# JETSON.net
KiCad netlist of a schematic drawn in Altium Designer
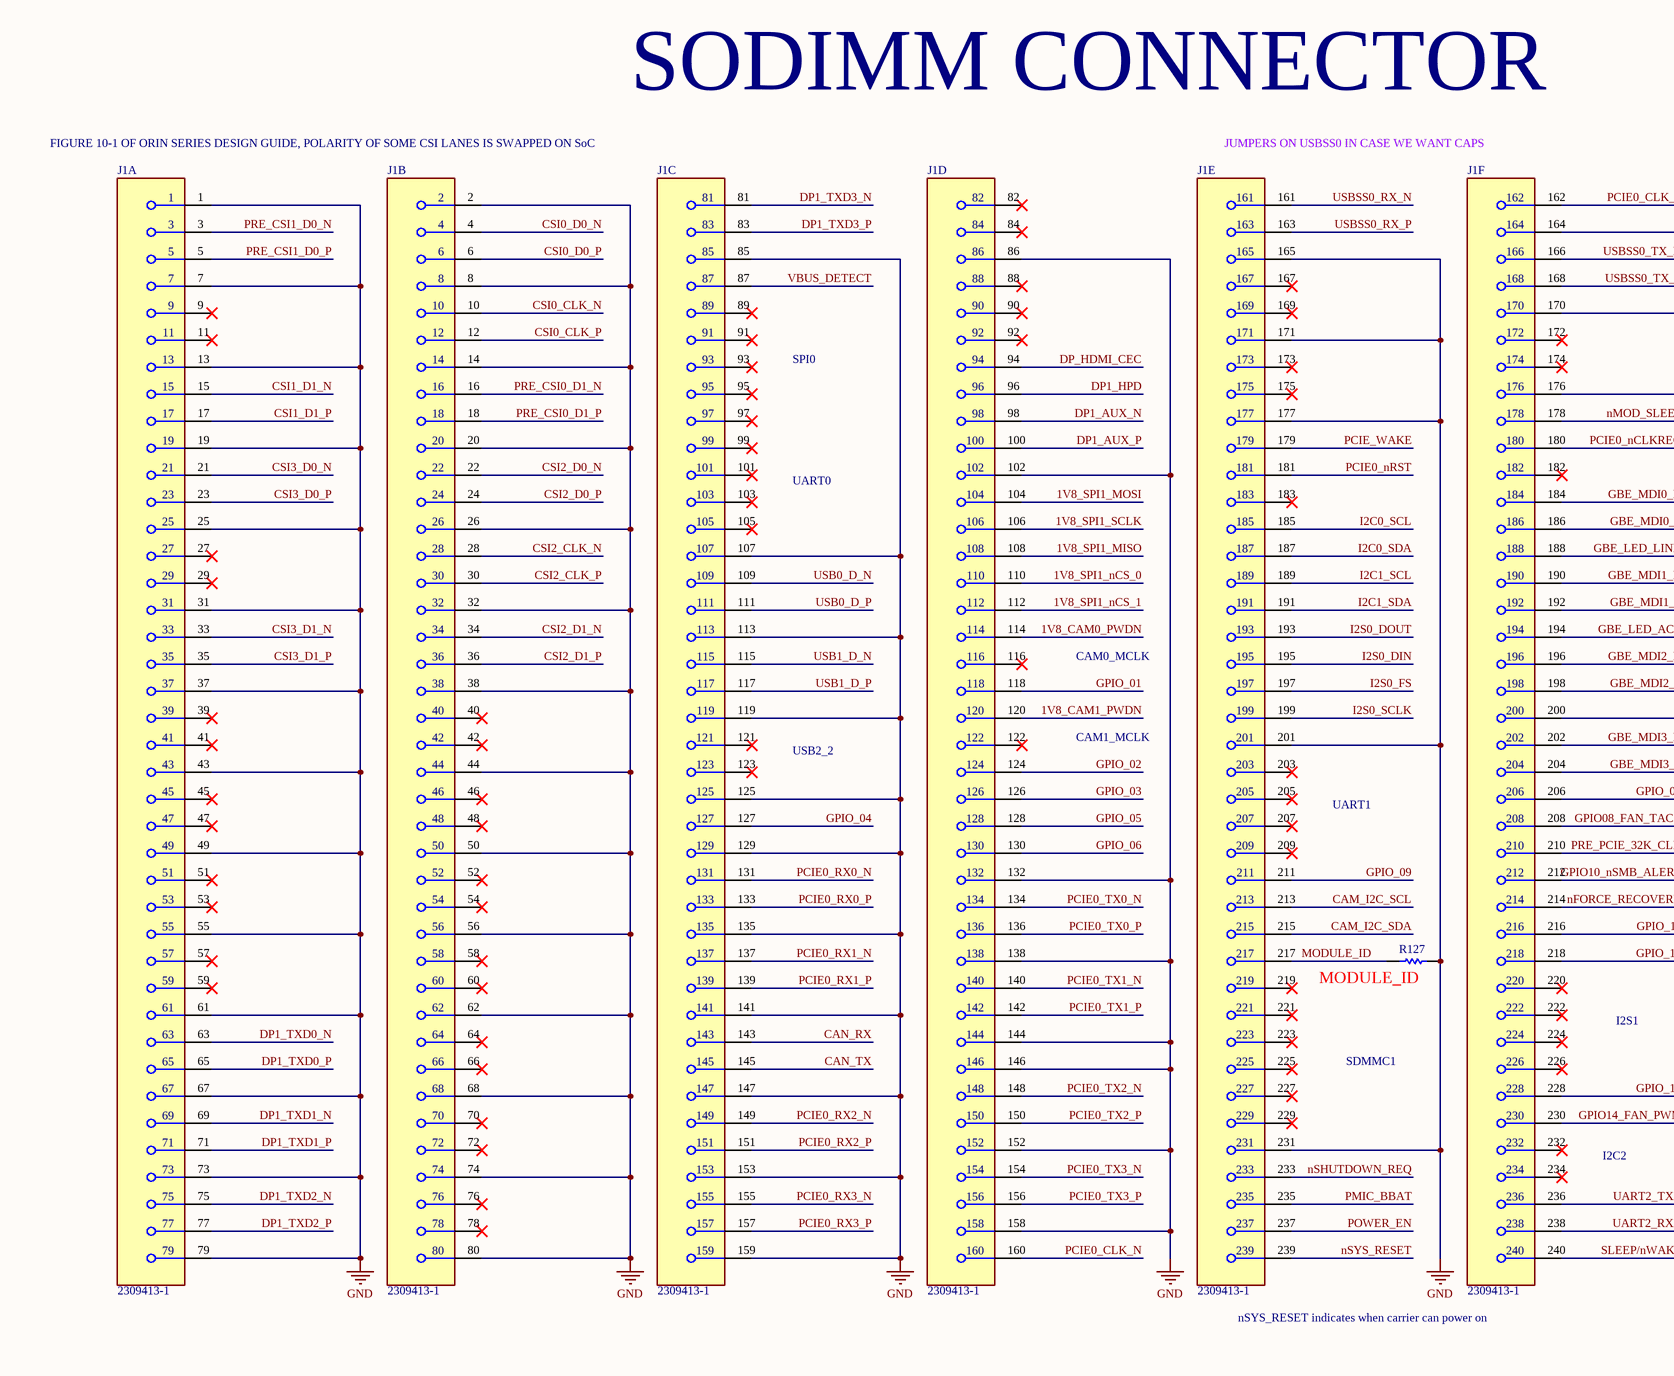
[diagram p0: JETSON.SchDoc, top left]
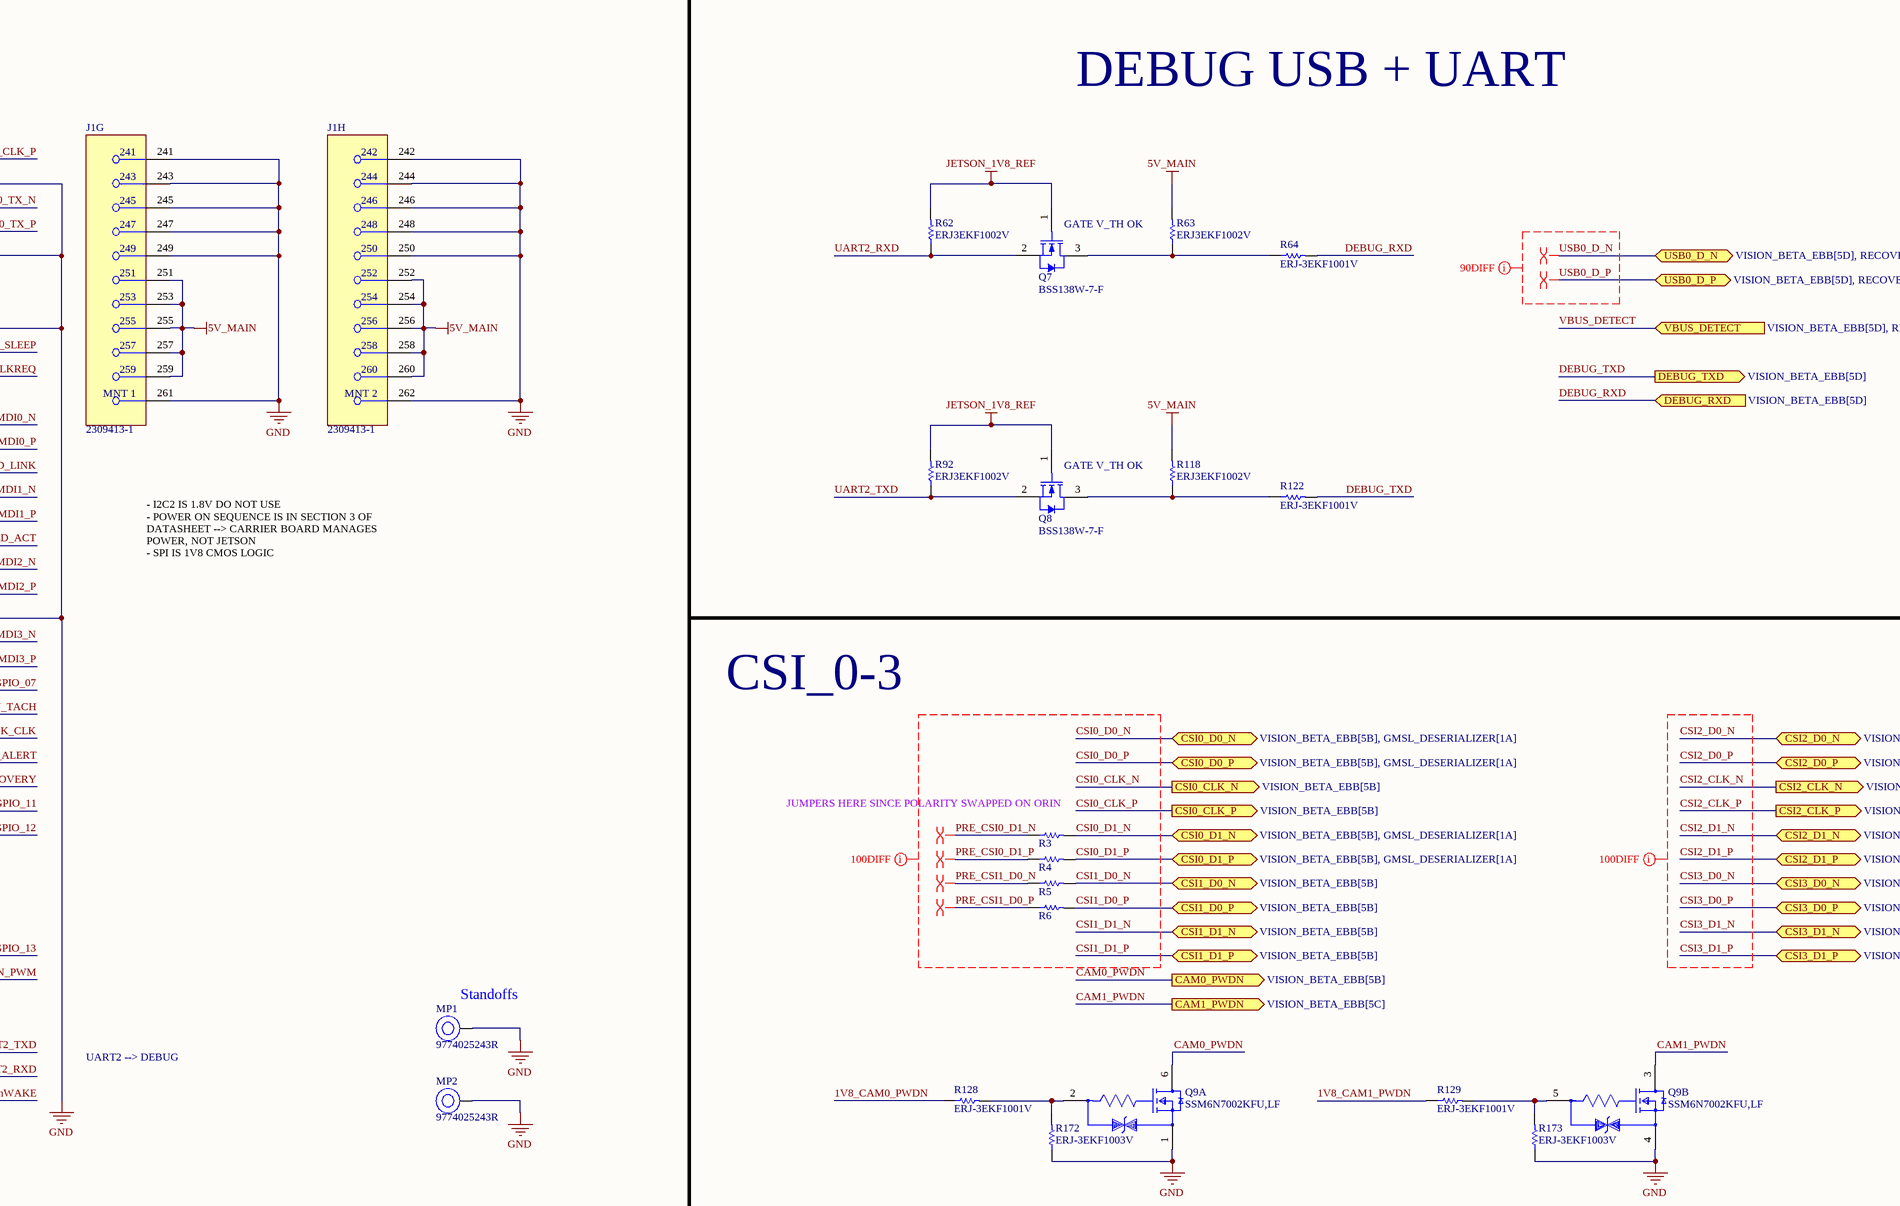
[diagram p1: JETSON.SchDoc, top middle]
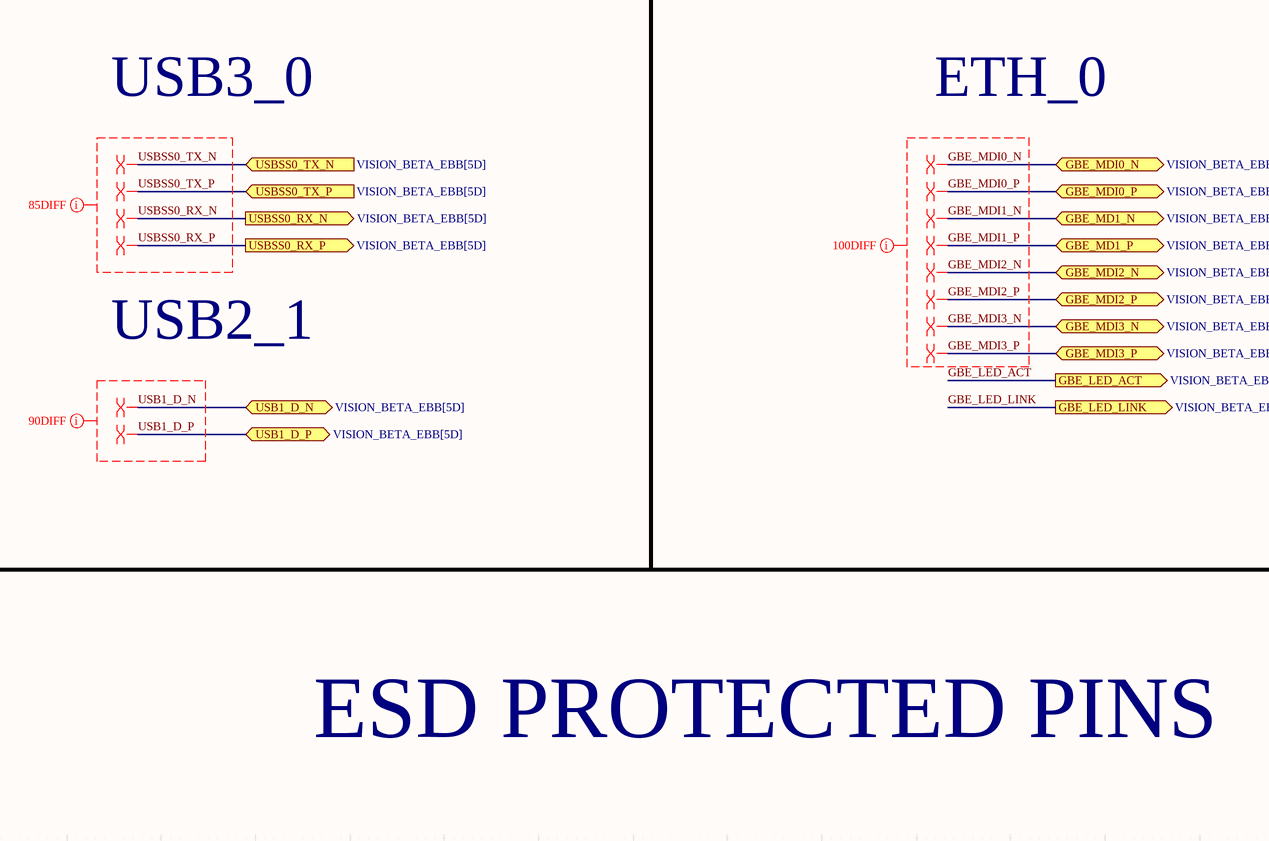
[diagram p2: JETSON.SchDoc, top right]
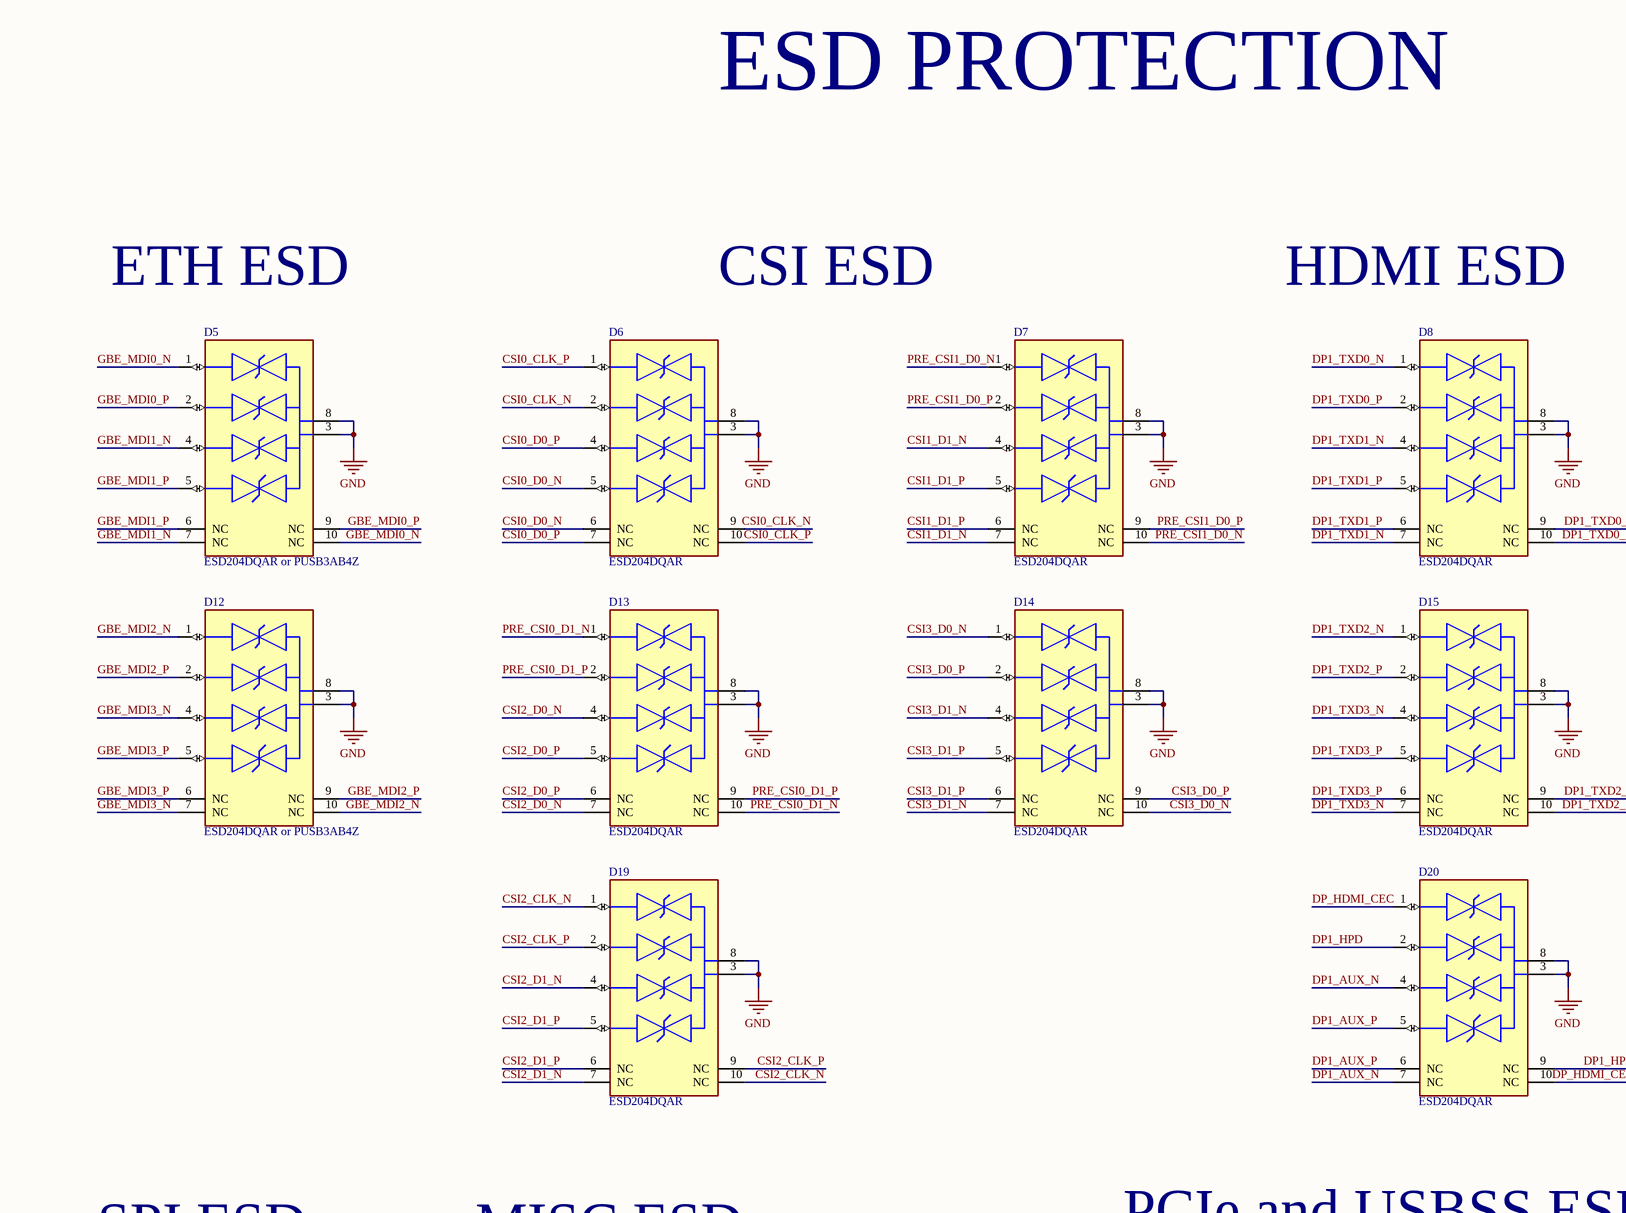
[diagram p3: JETSON.SchDoc, centre left]
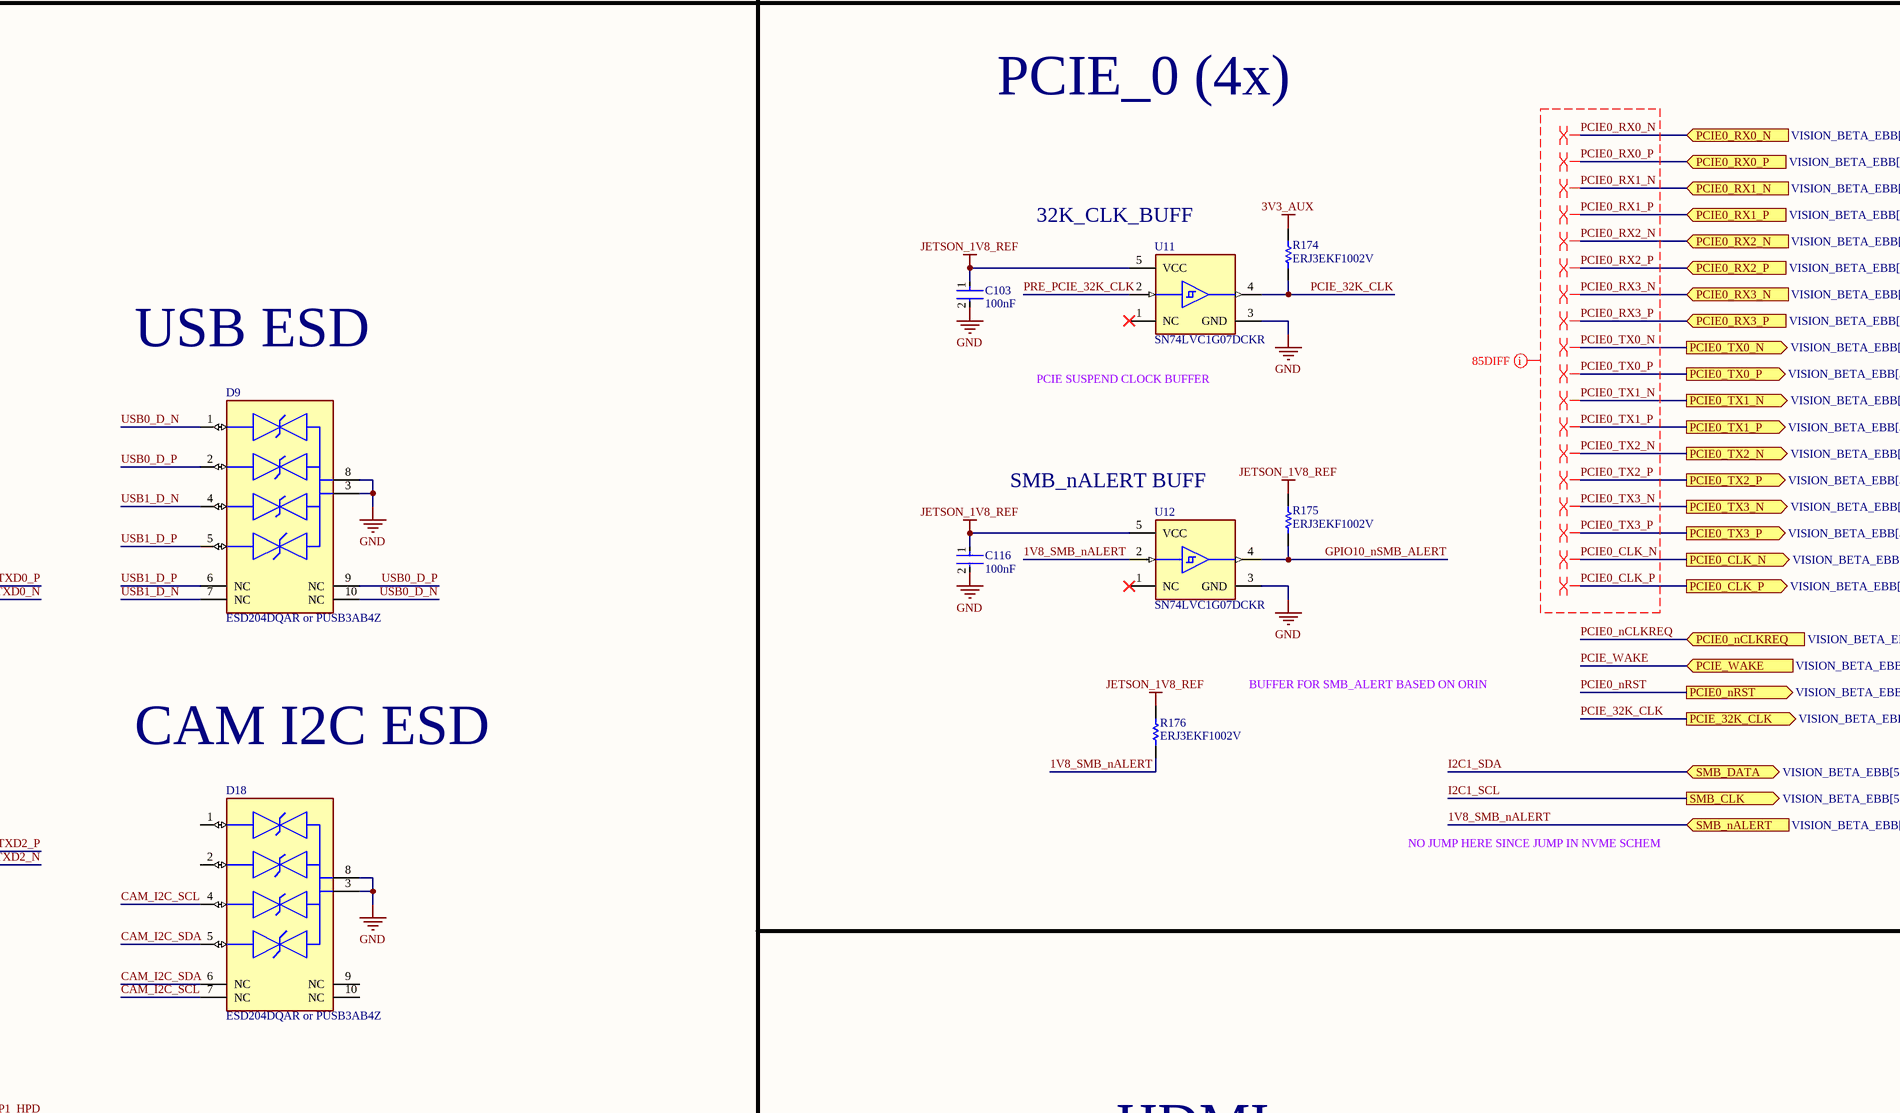
[diagram p4: JETSON.SchDoc, centre middle]
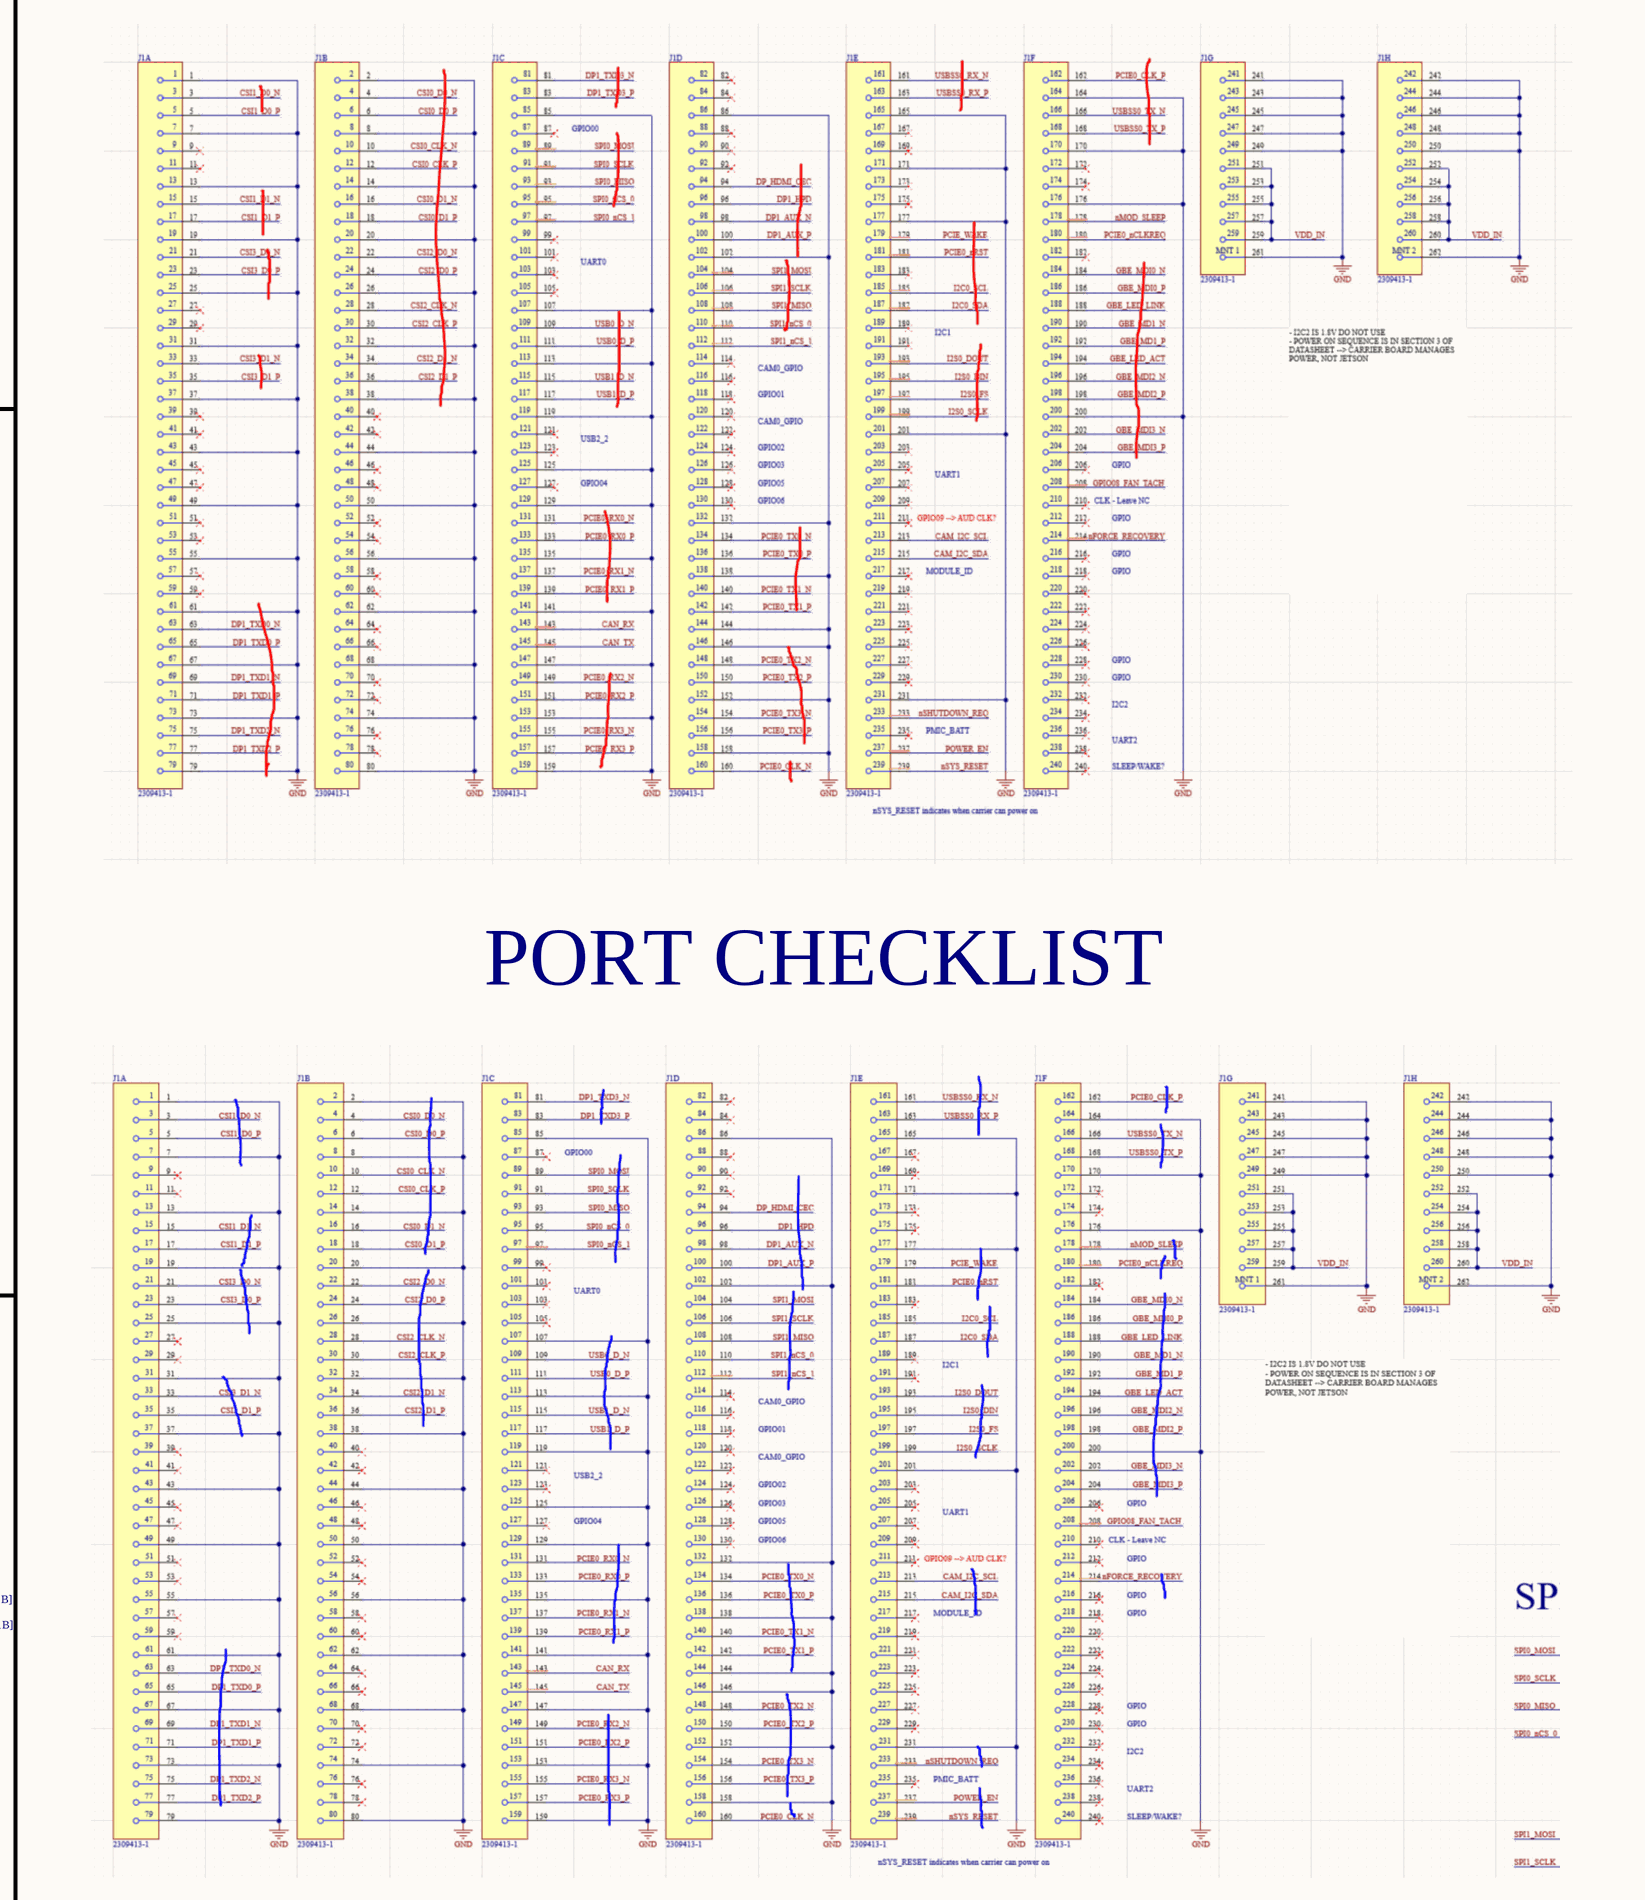
[diagram p5: JETSON.SchDoc, centre right]
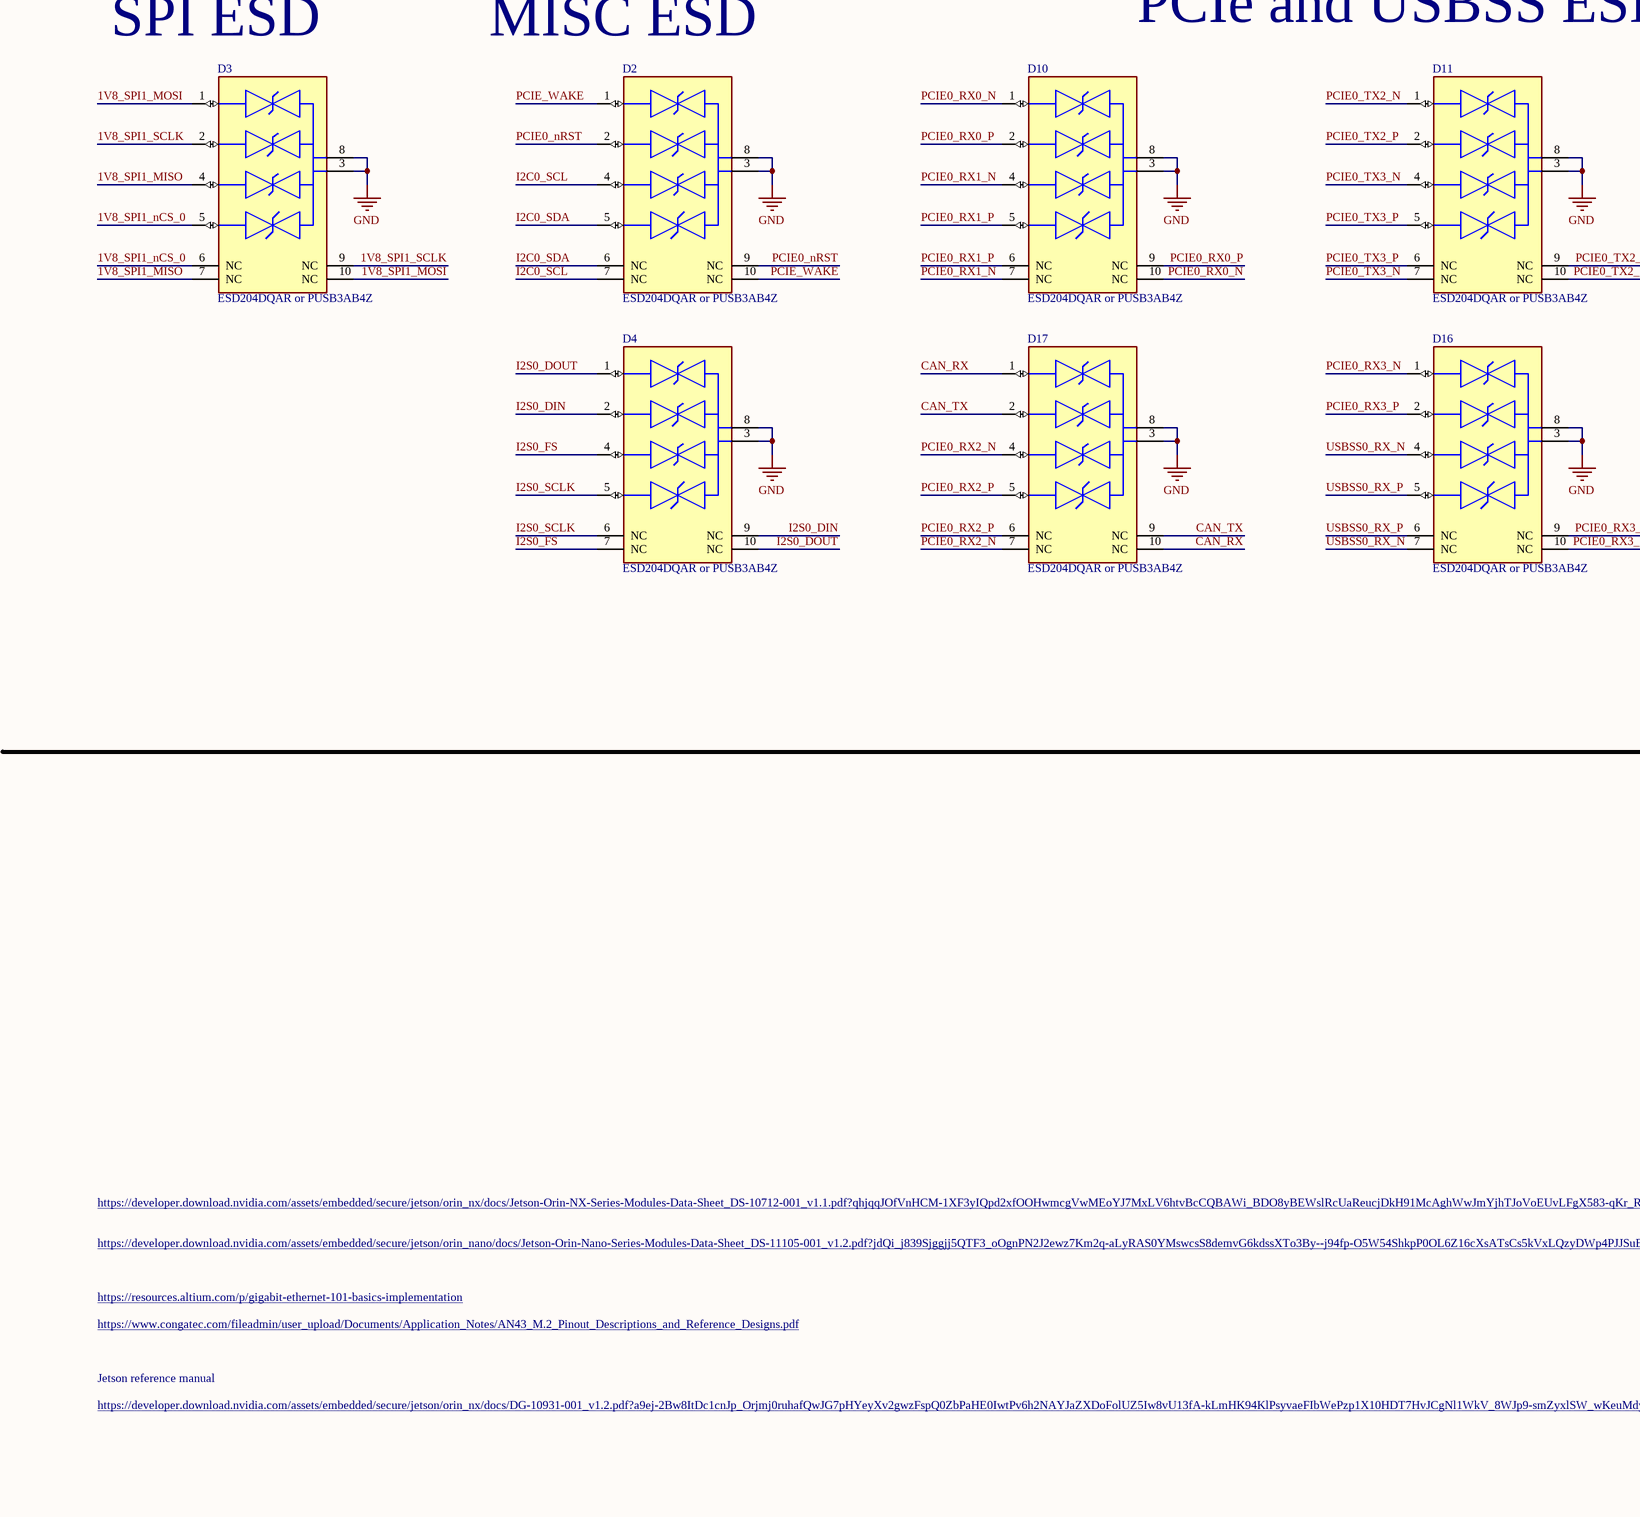
[diagram p6: JETSON.SchDoc, bottom left]
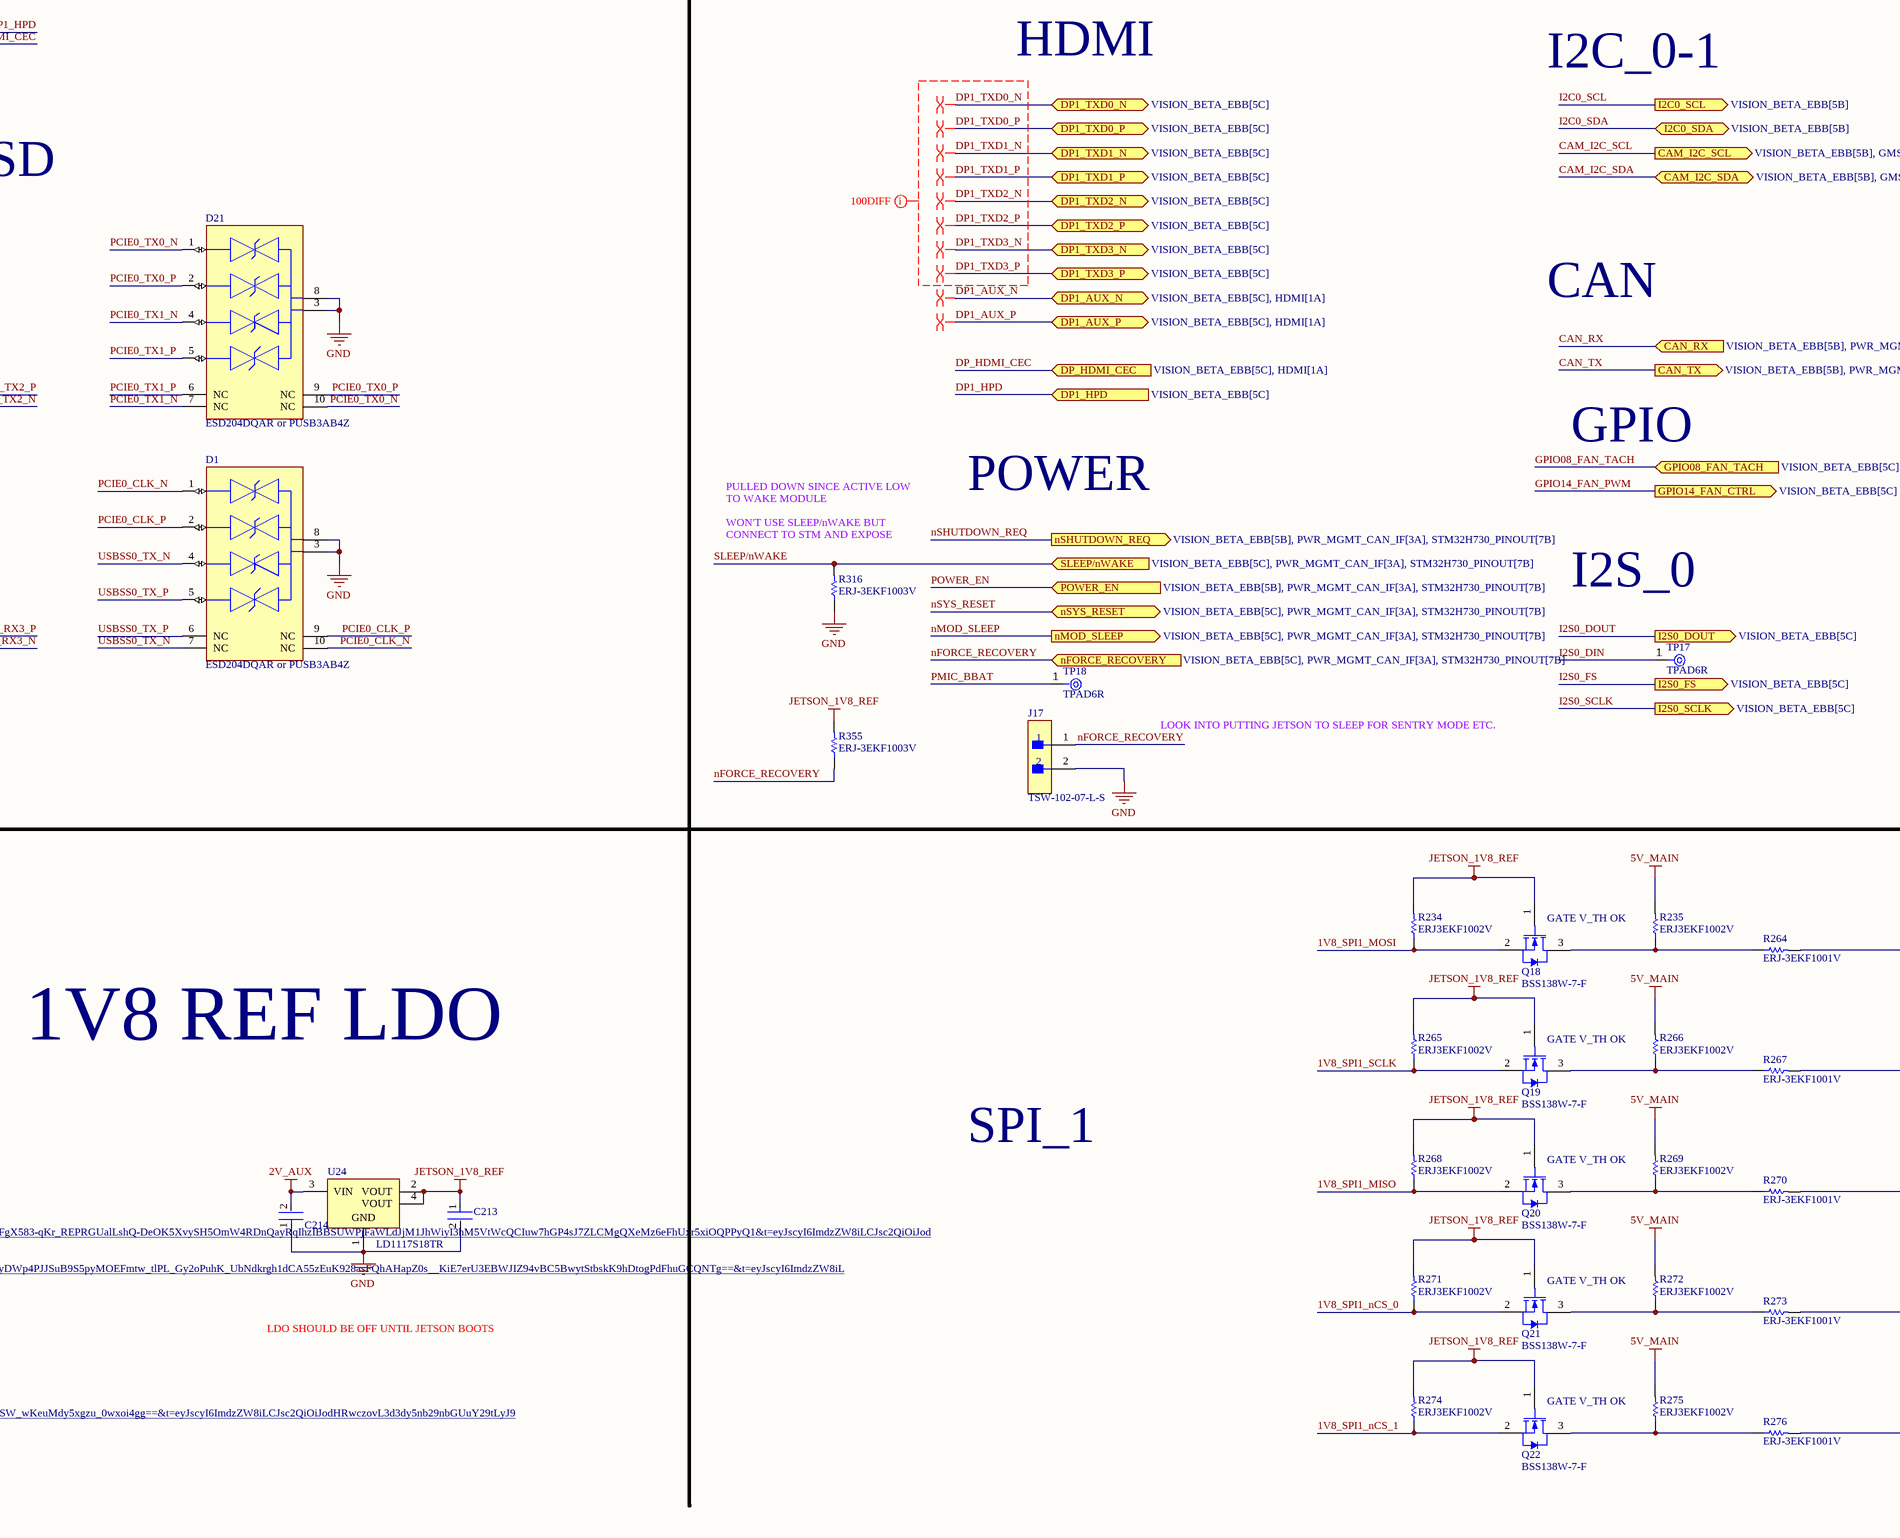
[diagram p7: JETSON.SchDoc, bottom middle]
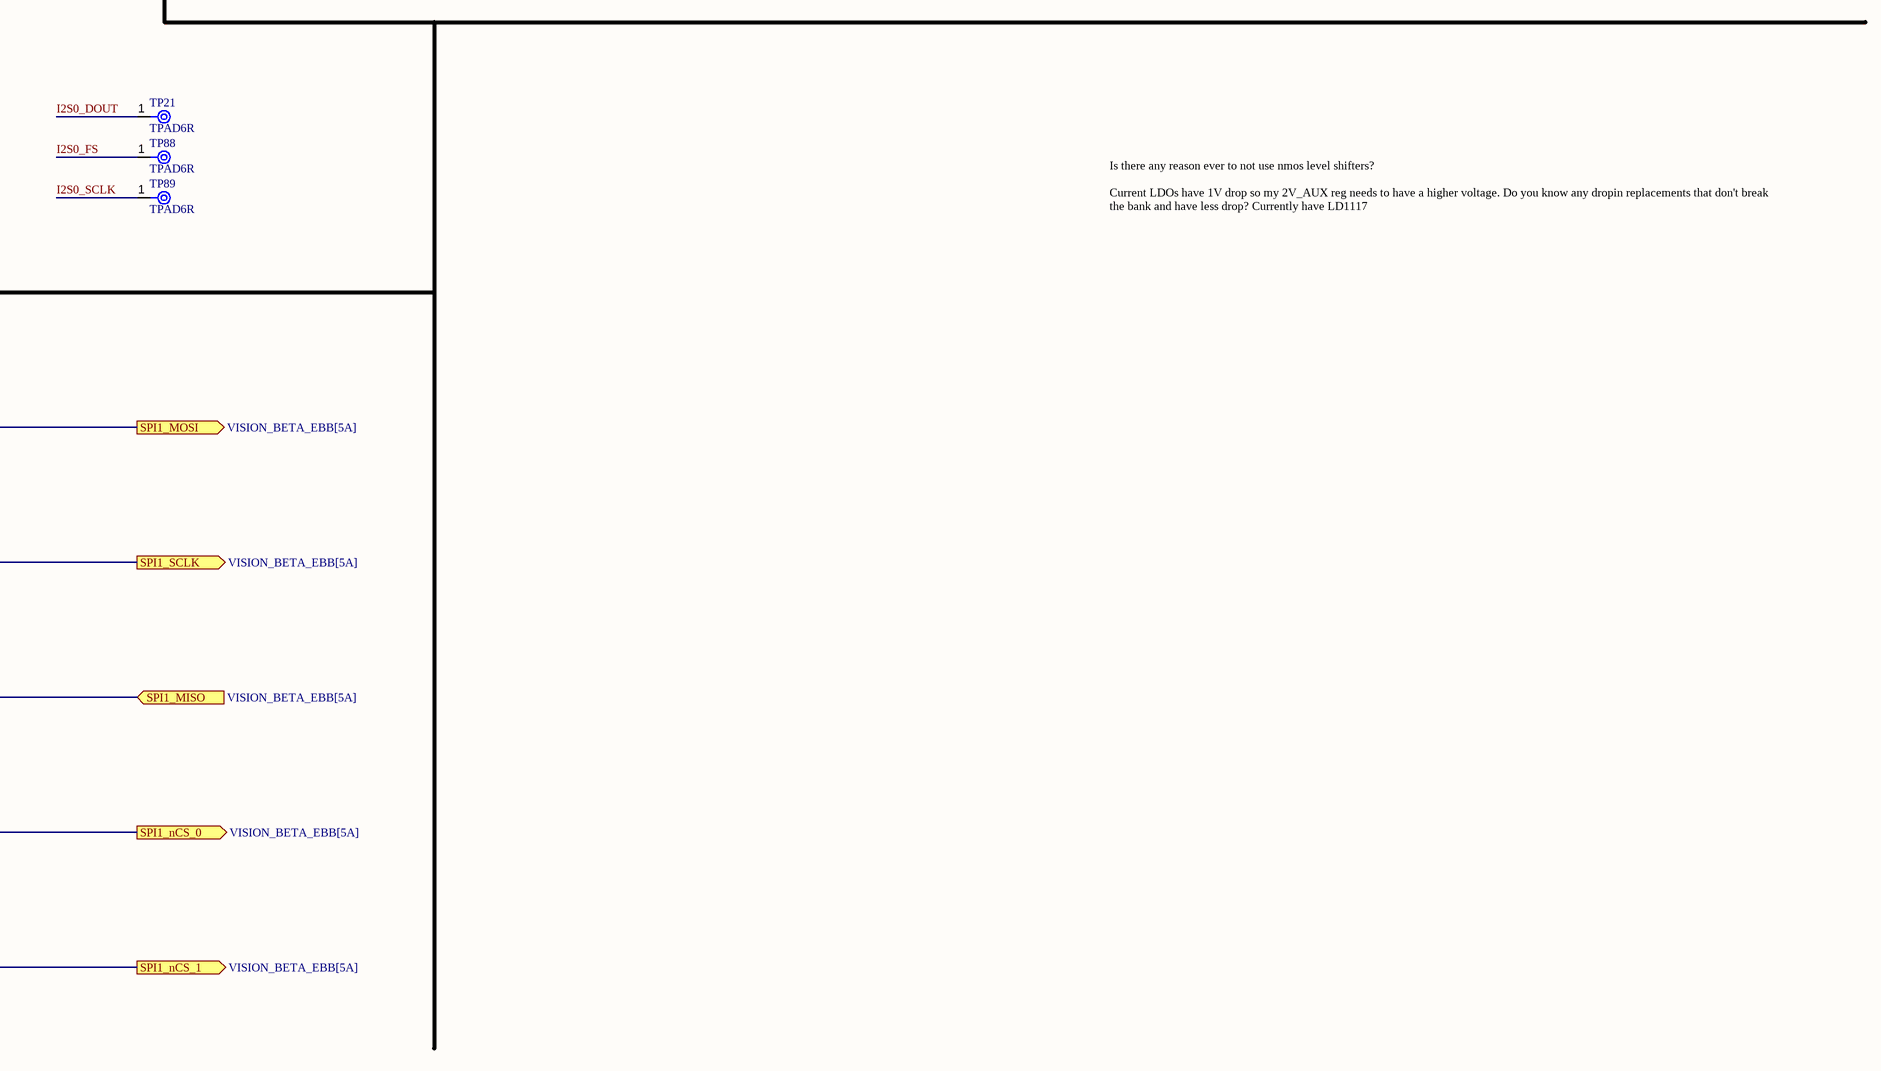
[diagram p8: JETSON.SchDoc, bottom right]

(export (version "E")
  (design (tool "Eeschema 10.0.6"))
  (components
    (comp (ref "C103")
      (value "100nF")
      (footprint "FP-0402-L_1_0_0_05-W_0_5-IPC_A")
      (description "LARGE PADS, 0402 CAP, CHANGE COMMENT TO MATCH REAL P/N")
      (libsource (lib "Space Concordia") (part "b4654b650e69147ec39a6b967a45e02"))
    )
    (comp (ref "C116")
      (value "100nF")
      (footprint "FP-0402-L_1_0_0_05-W_0_5-IPC_A")
      (description "LARGE PADS, 0402 CAP, CHANGE COMMENT TO MATCH REAL P/N")
      (libsource (lib "Space Concordia") (part "b4654b650e69147ec39a6b967a45e02"))
    )
    (comp (ref "C213")
      (value "GRM188R60J106ME47D")
      (footprint "FP-GRM188-0_1-e0_2_0_55-IPC_A")
      (description "Chip Multilayer Ceramic Capacitors for General Purpose, 0603, 10uF, X5R, 15%, 20%, 6.3V")
      (fields (field (name "VOLTAGE") "6.3V") (field (name "TOLERANCE") "20%"))
      (libsource (lib "Altium Content Vault") (part "02cd4be3c70576c341d710602a673aa"))
    )
    (comp (ref "C214")
      (value "C1005X7R1H104K050BB")
      (footprint "FP-C1005-050-0_05-IPC_C")
      (description "Multilayer Ceramic Capacitors 100nF ±10% 50V X7R SMD 0402")
      (fields (field (name "VOLTAGE") "50V") (field (name "TOLERANCE") "10%"))
      (libsource (lib "Altium Content Vault") (part "b4654b650e69147ec39a6b967a45e02"))
    )
    (comp (ref "D1")
      (value "ESD204DQAR or PUSB3AB4Z")
      (footprint "FP-DQA0010A-MFG")
      (description "4-CHANNEL LOW-CAPACITANCE SURGE")
      (fields
        (field (name "MANUFACTURER") "Texas Instruments")
        (field (name "OCTOPART") "https://octopart.com/esd204dqar-texas+instruments-89917476")
      )
      (libsource (lib "Altium Content Vault") (part "1465e58c1818c7767b55926832f0bf5"))
    )
    (comp (ref "D2")
      (value "ESD204DQAR or PUSB3AB4Z")
      (footprint "FP-DQA0010A-MFG")
      (description "4-CHANNEL LOW-CAPACITANCE SURGE")
      (fields
        (field (name "MANUFACTURER") "Texas Instruments")
        (field (name "OCTOPART") "https://octopart.com/esd204dqar-texas+instruments-89917476")
      )
      (libsource (lib "Altium Content Vault") (part "1465e58c1818c7767b55926832f0bf5"))
    )
    (comp (ref "D3")
      (value "ESD204DQAR or PUSB3AB4Z")
      (footprint "FP-DQA0010A-MFG")
      (description "4-CHANNEL LOW-CAPACITANCE SURGE")
      (fields
        (field (name "MANUFACTURER") "Texas Instruments")
        (field (name "OCTOPART") "https://octopart.com/esd204dqar-texas+instruments-89917476")
      )
      (libsource (lib "Altium Content Vault") (part "1465e58c1818c7767b55926832f0bf5"))
    )
    (comp (ref "D4")
      (value "ESD204DQAR or PUSB3AB4Z")
      (footprint "FP-DQA0010A-MFG")
      (description "4-CHANNEL LOW-CAPACITANCE SURGE")
      (fields
        (field (name "MANUFACTURER") "Texas Instruments")
        (field (name "OCTOPART") "https://octopart.com/esd204dqar-texas+instruments-89917476")
      )
      (libsource (lib "Altium Content Vault") (part "1465e58c1818c7767b55926832f0bf5"))
    )
    (comp (ref "D5")
      (value "ESD204DQAR or PUSB3AB4Z")
      (footprint "FP-DQA0010A-MFG")
      (description "4-CHANNEL LOW-CAPACITANCE SURGE")
      (fields
        (field (name "MANUFACTURER") "Texas Instruments")
        (field (name "OCTOPART") "https://octopart.com/esd204dqar-texas+instruments-89917476")
      )
      (libsource (lib "Altium Content Vault") (part "1465e58c1818c7767b55926832f0bf5"))
    )
    (comp (ref "D6")
      (value "ESD204DQAR")
      (footprint "FP-DQA0010A-MFG")
      (description "4-CHANNEL LOW-CAPACITANCE SURGE")
      (fields
        (field (name "MANUFACTURER") "Texas Instruments")
        (field (name "OCTOPART") "https://octopart.com/esd204dqar-texas+instruments-89917476")
      )
      (libsource (lib "Altium Content Vault") (part "1465e58c1818c7767b55926832f0bf5"))
    )
    (comp (ref "D7")
      (value "ESD204DQAR")
      (footprint "FP-DQA0010A-MFG")
      (description "4-CHANNEL LOW-CAPACITANCE SURGE")
      (fields
        (field (name "MANUFACTURER") "Texas Instruments")
        (field (name "OCTOPART") "https://octopart.com/esd204dqar-texas+instruments-89917476")
      )
      (libsource (lib "Altium Content Vault") (part "1465e58c1818c7767b55926832f0bf5"))
    )
    (comp (ref "D8")
      (value "ESD204DQAR")
      (footprint "FP-DQA0010A-MFG")
      (description "4-CHANNEL LOW-CAPACITANCE SURGE")
      (fields
        (field (name "MANUFACTURER") "Texas Instruments")
        (field (name "OCTOPART") "https://octopart.com/esd204dqar-texas+instruments-89917476")
      )
      (libsource (lib "Altium Content Vault") (part "1465e58c1818c7767b55926832f0bf5"))
    )
    (comp (ref "D9")
      (value "ESD204DQAR or PUSB3AB4Z")
      (footprint "FP-DQA0010A-MFG")
      (description "4-CHANNEL LOW-CAPACITANCE SURGE")
      (fields
        (field (name "MANUFACTURER") "Texas Instruments")
        (field (name "OCTOPART") "https://octopart.com/esd204dqar-texas+instruments-89917476")
      )
      (libsource (lib "Altium Content Vault") (part "1465e58c1818c7767b55926832f0bf5"))
    )
    (comp (ref "D10")
      (value "ESD204DQAR or PUSB3AB4Z")
      (footprint "FP-DQA0010A-MFG")
      (description "4-CHANNEL LOW-CAPACITANCE SURGE")
      (fields
        (field (name "MANUFACTURER") "Texas Instruments")
        (field (name "OCTOPART") "https://octopart.com/esd204dqar-texas+instruments-89917476")
      )
      (libsource (lib "Altium Content Vault") (part "1465e58c1818c7767b55926832f0bf5"))
    )
    (comp (ref "D11")
      (value "ESD204DQAR or PUSB3AB4Z")
      (footprint "FP-DQA0010A-MFG")
      (description "4-CHANNEL LOW-CAPACITANCE SURGE")
      (fields
        (field (name "MANUFACTURER") "Texas Instruments")
        (field (name "OCTOPART") "https://octopart.com/esd204dqar-texas+instruments-89917476")
      )
      (libsource (lib "Altium Content Vault") (part "1465e58c1818c7767b55926832f0bf5"))
    )
    (comp (ref "D12")
      (value "ESD204DQAR or PUSB3AB4Z")
      (footprint "FP-DQA0010A-MFG")
      (description "4-CHANNEL LOW-CAPACITANCE SURGE")
      (fields
        (field (name "MANUFACTURER") "Texas Instruments")
        (field (name "OCTOPART") "https://octopart.com/esd204dqar-texas+instruments-89917476")
      )
      (libsource (lib "Altium Content Vault") (part "1465e58c1818c7767b55926832f0bf5"))
    )
    (comp (ref "D13")
      (value "ESD204DQAR")
      (footprint "FP-DQA0010A-MFG")
      (description "4-CHANNEL LOW-CAPACITANCE SURGE")
      (fields
        (field (name "MANUFACTURER") "Texas Instruments")
        (field (name "OCTOPART") "https://octopart.com/esd204dqar-texas+instruments-89917476")
      )
      (libsource (lib "Altium Content Vault") (part "1465e58c1818c7767b55926832f0bf5"))
    )
    (comp (ref "D14")
      (value "ESD204DQAR")
      (footprint "FP-DQA0010A-MFG")
      (description "4-CHANNEL LOW-CAPACITANCE SURGE")
      (fields
        (field (name "MANUFACTURER") "Texas Instruments")
        (field (name "OCTOPART") "https://octopart.com/esd204dqar-texas+instruments-89917476")
      )
      (libsource (lib "Altium Content Vault") (part "1465e58c1818c7767b55926832f0bf5"))
    )
    (comp (ref "D15")
      (value "ESD204DQAR")
      (footprint "FP-DQA0010A-MFG")
      (description "4-CHANNEL LOW-CAPACITANCE SURGE")
      (fields
        (field (name "MANUFACTURER") "Texas Instruments")
        (field (name "OCTOPART") "https://octopart.com/esd204dqar-texas+instruments-89917476")
      )
      (libsource (lib "Altium Content Vault") (part "1465e58c1818c7767b55926832f0bf5"))
    )
    (comp (ref "D16")
      (value "ESD204DQAR or PUSB3AB4Z")
      (footprint "FP-DQA0010A-MFG")
      (description "4-CHANNEL LOW-CAPACITANCE SURGE")
      (fields
        (field (name "MANUFACTURER") "Texas Instruments")
        (field (name "OCTOPART") "https://octopart.com/esd204dqar-texas+instruments-89917476")
      )
      (libsource (lib "Altium Content Vault") (part "1465e58c1818c7767b55926832f0bf5"))
    )
    (comp (ref "D17")
      (value "ESD204DQAR or PUSB3AB4Z")
      (footprint "FP-DQA0010A-MFG")
      (description "4-CHANNEL LOW-CAPACITANCE SURGE")
      (fields
        (field (name "MANUFACTURER") "Texas Instruments")
        (field (name "OCTOPART") "https://octopart.com/esd204dqar-texas+instruments-89917476")
      )
      (libsource (lib "Altium Content Vault") (part "1465e58c1818c7767b55926832f0bf5"))
    )
    (comp (ref "D18")
      (value "ESD204DQAR or PUSB3AB4Z")
      (footprint "FP-DQA0010A-MFG")
      (description "4-CHANNEL LOW-CAPACITANCE SURGE")
      (fields
        (field (name "MANUFACTURER") "Texas Instruments")
        (field (name "OCTOPART") "https://octopart.com/esd204dqar-texas+instruments-89917476")
      )
      (libsource (lib "Altium Content Vault") (part "1465e58c1818c7767b55926832f0bf5"))
    )
    (comp (ref "D19")
      (value "ESD204DQAR")
      (footprint "FP-DQA0010A-MFG")
      (description "4-CHANNEL LOW-CAPACITANCE SURGE")
      (fields
        (field (name "MANUFACTURER") "Texas Instruments")
        (field (name "OCTOPART") "https://octopart.com/esd204dqar-texas+instruments-89917476")
      )
      (libsource (lib "Altium Content Vault") (part "1465e58c1818c7767b55926832f0bf5"))
    )
    (comp (ref "D20")
      (value "ESD204DQAR")
      (footprint "FP-DQA0010A-MFG")
      (description "4-CHANNEL LOW-CAPACITANCE SURGE")
      (fields
        (field (name "MANUFACTURER") "Texas Instruments")
        (field (name "OCTOPART") "https://octopart.com/esd204dqar-texas+instruments-89917476")
      )
      (libsource (lib "Altium Content Vault") (part "1465e58c1818c7767b55926832f0bf5"))
    )
    (comp (ref "D21")
      (value "ESD204DQAR or PUSB3AB4Z")
      (footprint "FP-DQA0010A-MFG")
      (description "4-CHANNEL LOW-CAPACITANCE SURGE")
      (fields
        (field (name "MANUFACTURER") "Texas Instruments")
        (field (name "OCTOPART") "https://octopart.com/esd204dqar-texas+instruments-89917476")
      )
      (libsource (lib "Altium Content Vault") (part "1465e58c1818c7767b55926832f0bf5"))
    )
    (comp (ref "J1")
      (value "2309413-1")
      (footprint "FP-2309413-1-MFG")
      (description "DDR4 SODIMM 260P 9.2H STD")
      (fields
        (field (name "OCTOPART") "https://octopart.com/2309413-1-te+connectivity-84799194")
        (field (name "MANUFACTURER") "TE Connectivity")
      )
      (libsource (lib "Altium Content Vault") (part "4d1075b24ee2591bdcd47d674b3d2aa"))
    )
    (comp (ref "J17")
      (value "TSW-102-07-L-S")
      (footprint "FP-TSW-102-07-L-S-MFG")
      (description "CONN HEADER VERT 2POS 2.54MM")
      (libsource (lib "Altium Content Vault") (part "3bc925449376181038e59eaffc5286c"))
    )
    (comp (ref "MP1")
      (value "9774025243R")
      (footprint "9774025243")
      (description "9774025243R Spacer Material: Steel, Tin-Plated Mounting: SMT Series: WA-SMST Thread D: M2")
      (libsource (lib "Altium Content Vault") (part "Spacer"))
    )
    (comp (ref "MP2")
      (value "9774025243R")
      (footprint "9774025243")
      (description "9774025243R Spacer Material: Steel, Tin-Plated Mounting: SMT Series: WA-SMST Thread D: M2")
      (libsource (lib "Altium Content Vault") (part "Spacer"))
    )
    (comp (ref "Q7")
      (value "BSS138W-7-F")
      (footprint "DIOD-SOT323-3_V")
      (fields (field (name "MANUFACTURER") "DiodesIncorporated"))
      (libsource (lib "Altium Content Vault") (part "NEMOS-GSD-3"))
    )
    (comp (ref "Q8")
      (value "BSS138W-7-F")
      (footprint "DIOD-SOT323-3_V")
      (fields (field (name "MANUFACTURER") "DiodesIncorporated"))
      (libsource (lib "Altium Content Vault") (part "NEMOS-GSD-3"))
    )
    (comp (ref "Q9")
      (value "SSM6N7002KFU,LF")
      (footprint "FP-SSOP6-P-0_65A-MFG")
      (description "MOSFET 2N-CH 60V 0.3A")
      (libsource (lib "Altium Content Vault") (part "088aa6ac103fdeebe0d1c52ece6b7b9"))
    )
    (comp (ref "Q18")
      (value "BSS138W-7-F")
      (footprint "DIOD-SOT323-3_V")
      (fields (field (name "MANUFACTURER") "DiodesIncorporated"))
      (libsource (lib "Altium Content Vault") (part "NEMOS-GSD-3"))
    )
    (comp (ref "Q19")
      (value "BSS138W-7-F")
      (footprint "DIOD-SOT323-3_V")
      (fields (field (name "MANUFACTURER") "DiodesIncorporated"))
      (libsource (lib "Altium Content Vault") (part "NEMOS-GSD-3"))
    )
    (comp (ref "Q20")
      (value "BSS138W-7-F")
      (footprint "DIOD-SOT323-3_V")
      (fields (field (name "MANUFACTURER") "DiodesIncorporated"))
      (libsource (lib "Altium Content Vault") (part "NEMOS-GSD-3"))
    )
    (comp (ref "Q21")
      (value "BSS138W-7-F")
      (footprint "DIOD-SOT323-3_V")
      (fields (field (name "MANUFACTURER") "DiodesIncorporated"))
      (libsource (lib "Altium Content Vault") (part "NEMOS-GSD-3"))
    )
    (comp (ref "Q22")
      (value "BSS138W-7-F")
      (footprint "DIOD-SOT323-3_V")
      (fields (field (name "MANUFACTURER") "DiodesIncorporated"))
      (libsource (lib "Altium Content Vault") (part "NEMOS-GSD-3"))
    )
    (comp (ref "R3")
      (value "0402 JUMPER")
      (footprint "RESC1005X40X25ML05T05")
      (description "READ THE NAME")
      (libsource (lib "Space Concordia") (part "CMP-009-00206-2"))
    )
    (comp (ref "R4")
      (value "0402 JUMPER")
      (footprint "RESC1005X40X25ML05T05")
      (description "READ THE NAME")
      (libsource (lib "Space Concordia") (part "CMP-009-00206-2"))
    )
    (comp (ref "R5")
      (value "0402 JUMPER")
      (footprint "RESC1005X40X25ML05T05")
      (description "READ THE NAME")
      (libsource (lib "Space Concordia") (part "CMP-009-00206-2"))
    )
    (comp (ref "R6")
      (value "0402 JUMPER")
      (footprint "RESC1005X40X25ML05T05")
      (description "READ THE NAME")
      (libsource (lib "Space Concordia") (part "CMP-009-00206-2"))
    )
    (comp (ref "R62")
      (value "ERJ3EKF1002V")
      (footprint "RESC1609X55X30LL15T15")
      (description "Chip Resistor, 10 KOhm, +/- 1%, 0.1 W, -55 to 155 degC, 0603 (1608 Metric), RoHS, Tape and Reel")
      (fields (field (name "TOLERANCE") "1%") (field (name "MANUFACTURER") "Panasonic"))
      (libsource (lib "Altium Content Vault") (part "RES-2"))
    )
    (comp (ref "R63")
      (value "ERJ3EKF1002V")
      (footprint "RESC1609X55X30LL15T15")
      (description "Chip Resistor, 10 KOhm, +/- 1%, 0.1 W, -55 to 155 degC, 0603 (1608 Metric), RoHS, Tape and Reel")
      (fields (field (name "TOLERANCE") "1%") (field (name "MANUFACTURER") "Panasonic"))
      (libsource (lib "Altium Content Vault") (part "RES-2"))
    )
    (comp (ref "R64")
      (value "ERJ-3EKF1001V")
      (footprint "RESC1608X55X30LL15T15")
      (fields (field (name "MANUFACTURER") "Panasonic"))
      (libsource (lib "Altium Content Vault") (part "RES"))
    )
    (comp (ref "R92")
      (value "ERJ3EKF1002V")
      (footprint "RESC1609X55X30LL15T15")
      (description "Chip Resistor, 10 KOhm, +/- 1%, 0.1 W, -55 to 155 degC, 0603 (1608 Metric), RoHS, Tape and Reel")
      (fields (field (name "TOLERANCE") "1%") (field (name "MANUFACTURER") "Panasonic"))
      (libsource (lib "Altium Content Vault") (part "RES-2"))
    )
    (comp (ref "R118")
      (value "ERJ3EKF1002V")
      (footprint "RESC1609X55X30LL15T15")
      (description "Chip Resistor, 10 KOhm, +/- 1%, 0.1 W, -55 to 155 degC, 0603 (1608 Metric), RoHS, Tape and Reel")
      (fields (field (name "TOLERANCE") "1%") (field (name "MANUFACTURER") "Panasonic"))
      (libsource (lib "Altium Content Vault") (part "RES-2"))
    )
    (comp (ref "R122")
      (value "ERJ-3EKF1001V")
      (footprint "RESC1608X55X30LL15T15")
      (fields (field (name "MANUFACTURER") "Panasonic"))
      (libsource (lib "Altium Content Vault") (part "RES"))
    )
    (comp (ref "R127")
      (value "0402 JUMPER")
      (footprint "RESC1005X40X25ML05T05")
      (description "READ THE NAME")
      (libsource (lib "Space Concordia") (part "CMP-009-00206-2"))
    )
    (comp (ref "R128")
      (value "ERJ-3EKF1001V")
      (footprint "RESC1608X55X30LL15T15")
      (fields (field (name "MANUFACTURER") "Panasonic"))
      (libsource (lib "Altium Content Vault") (part "RES"))
    )
    (comp (ref "R129")
      (value "ERJ-3EKF1001V")
      (footprint "RESC1608X55X30LL15T15")
      (fields (field (name "MANUFACTURER") "Panasonic"))
      (libsource (lib "Altium Content Vault") (part "RES"))
    )
    (comp (ref "R172")
      (value "ERJ-3EKF1003V")
      (footprint "RESC1608X55X30ML15T15")
      (fields (field (name "MANUFACTURER") "Panasonic"))
      (libsource (lib "Altium Content Vault") (part "RES"))
    )
    (comp (ref "R173")
      (value "ERJ-3EKF1003V")
      (footprint "RESC1608X55X30ML15T15")
      (fields (field (name "MANUFACTURER") "Panasonic"))
      (libsource (lib "Altium Content Vault") (part "RES"))
    )
    (comp (ref "R174")
      (value "ERJ3EKF1002V")
      (footprint "RESC1609X55X30LL15T15")
      (description "Chip Resistor, 10 KOhm, +/- 1%, 0.1 W, -55 to 155 degC, 0603 (1608 Metric), RoHS, Tape and Reel")
      (fields (field (name "TOLERANCE") "1%") (field (name "MANUFACTURER") "Panasonic"))
      (libsource (lib "Altium Content Vault") (part "RES-2"))
    )
    (comp (ref "R175")
      (value "ERJ3EKF1002V")
      (footprint "RESC1609X55X30LL15T15")
      (description "Chip Resistor, 10 KOhm, +/- 1%, 0.1 W, -55 to 155 degC, 0603 (1608 Metric), RoHS, Tape and Reel")
      (fields (field (name "TOLERANCE") "1%") (field (name "MANUFACTURER") "Panasonic"))
      (libsource (lib "Altium Content Vault") (part "RES-2"))
    )
    (comp (ref "R176")
      (value "ERJ3EKF1002V")
      (footprint "RESC1609X55X30LL15T15")
      (description "Chip Resistor, 10 KOhm, +/- 1%, 0.1 W, -55 to 155 degC, 0603 (1608 Metric), RoHS, Tape and Reel")
      (fields (field (name "TOLERANCE") "1%") (field (name "MANUFACTURER") "Panasonic"))
      (libsource (lib "Altium Content Vault") (part "RES-2"))
    )
    (comp (ref "R234")
      (value "ERJ3EKF1002V")
      (footprint "RESC1609X55X30LL15T15")
      (description "Chip Resistor, 10 KOhm, +/- 1%, 0.1 W, -55 to 155 degC, 0603 (1608 Metric), RoHS, Tape and Reel")
      (fields (field (name "TOLERANCE") "1%") (field (name "MANUFACTURER") "Panasonic"))
      (libsource (lib "Altium Content Vault") (part "RES-2"))
    )
    (comp (ref "R235")
      (value "ERJ3EKF1002V")
      (footprint "RESC1609X55X30LL15T15")
      (description "Chip Resistor, 10 KOhm, +/- 1%, 0.1 W, -55 to 155 degC, 0603 (1608 Metric), RoHS, Tape and Reel")
      (fields (field (name "TOLERANCE") "1%") (field (name "MANUFACTURER") "Panasonic"))
      (libsource (lib "Altium Content Vault") (part "RES-2"))
    )
    (comp (ref "R264")
      (value "ERJ-3EKF1001V")
      (footprint "RESC1608X55X30LL15T15")
      (fields (field (name "MANUFACTURER") "Panasonic"))
      (libsource (lib "Altium Content Vault") (part "RES"))
    )
    (comp (ref "R265")
      (value "ERJ3EKF1002V")
      (footprint "RESC1609X55X30LL15T15")
      (description "Chip Resistor, 10 KOhm, +/- 1%, 0.1 W, -55 to 155 degC, 0603 (1608 Metric), RoHS, Tape and Reel")
      (fields (field (name "TOLERANCE") "1%") (field (name "MANUFACTURER") "Panasonic"))
      (libsource (lib "Altium Content Vault") (part "RES-2"))
    )
    (comp (ref "R266")
      (value "ERJ3EKF1002V")
      (footprint "RESC1609X55X30LL15T15")
      (description "Chip Resistor, 10 KOhm, +/- 1%, 0.1 W, -55 to 155 degC, 0603 (1608 Metric), RoHS, Tape and Reel")
      (fields (field (name "TOLERANCE") "1%") (field (name "MANUFACTURER") "Panasonic"))
      (libsource (lib "Altium Content Vault") (part "RES-2"))
    )
    (comp (ref "R267")
      (value "ERJ-3EKF1001V")
      (footprint "RESC1608X55X30LL15T15")
      (fields (field (name "MANUFACTURER") "Panasonic"))
      (libsource (lib "Altium Content Vault") (part "RES"))
    )
    (comp (ref "R268")
      (value "ERJ3EKF1002V")
      (footprint "RESC1609X55X30LL15T15")
      (description "Chip Resistor, 10 KOhm, +/- 1%, 0.1 W, -55 to 155 degC, 0603 (1608 Metric), RoHS, Tape and Reel")
      (fields (field (name "TOLERANCE") "1%") (field (name "MANUFACTURER") "Panasonic"))
      (libsource (lib "Altium Content Vault") (part "RES-2"))
    )
    (comp (ref "R269")
      (value "ERJ3EKF1002V")
      (footprint "RESC1609X55X30LL15T15")
      (description "Chip Resistor, 10 KOhm, +/- 1%, 0.1 W, -55 to 155 degC, 0603 (1608 Metric), RoHS, Tape and Reel")
      (fields (field (name "TOLERANCE") "1%") (field (name "MANUFACTURER") "Panasonic"))
      (libsource (lib "Altium Content Vault") (part "RES-2"))
    )
    (comp (ref "R270")
      (value "ERJ-3EKF1001V")
      (footprint "RESC1608X55X30LL15T15")
      (fields (field (name "MANUFACTURER") "Panasonic"))
      (libsource (lib "Altium Content Vault") (part "RES"))
    )
    (comp (ref "R271")
      (value "ERJ3EKF1002V")
      (footprint "RESC1609X55X30LL15T15")
      (description "Chip Resistor, 10 KOhm, +/- 1%, 0.1 W, -55 to 155 degC, 0603 (1608 Metric), RoHS, Tape and Reel")
      (fields (field (name "TOLERANCE") "1%") (field (name "MANUFACTURER") "Panasonic"))
      (libsource (lib "Altium Content Vault") (part "RES-2"))
    )
    (comp (ref "R272")
      (value "ERJ3EKF1002V")
      (footprint "RESC1609X55X30LL15T15")
      (description "Chip Resistor, 10 KOhm, +/- 1%, 0.1 W, -55 to 155 degC, 0603 (1608 Metric), RoHS, Tape and Reel")
      (fields (field (name "TOLERANCE") "1%") (field (name "MANUFACTURER") "Panasonic"))
      (libsource (lib "Altium Content Vault") (part "RES-2"))
    )
    (comp (ref "R273")
      (value "ERJ-3EKF1001V")
      (footprint "RESC1608X55X30LL15T15")
      (fields (field (name "MANUFACTURER") "Panasonic"))
      (libsource (lib "Altium Content Vault") (part "RES"))
    )
    (comp (ref "R274")
      (value "ERJ3EKF1002V")
      (footprint "RESC1609X55X30LL15T15")
      (description "Chip Resistor, 10 KOhm, +/- 1%, 0.1 W, -55 to 155 degC, 0603 (1608 Metric), RoHS, Tape and Reel")
      (fields (field (name "TOLERANCE") "1%") (field (name "MANUFACTURER") "Panasonic"))
      (libsource (lib "Altium Content Vault") (part "RES-2"))
    )
    (comp (ref "R275")
      (value "ERJ3EKF1002V")
      (footprint "RESC1609X55X30LL15T15")
      (description "Chip Resistor, 10 KOhm, +/- 1%, 0.1 W, -55 to 155 degC, 0603 (1608 Metric), RoHS, Tape and Reel")
      (fields (field (name "TOLERANCE") "1%") (field (name "MANUFACTURER") "Panasonic"))
      (libsource (lib "Altium Content Vault") (part "RES-2"))
    )
    (comp (ref "R276")
      (value "ERJ-3EKF1001V")
      (footprint "RESC1608X55X30LL15T15")
      (fields (field (name "MANUFACTURER") "Panasonic"))
      (libsource (lib "Altium Content Vault") (part "RES"))
    )
    (comp (ref "R316")
      (value "ERJ-3EKF1003V")
      (footprint "RESC1608X55X30ML15T15")
      (fields (field (name "MANUFACTURER") "Panasonic"))
      (libsource (lib "Altium Content Vault") (part "RES"))
    )
    (comp (ref "R355")
      (value "ERJ-3EKF1003V")
      (footprint "RESC1608X55X30ML15T15")
      (fields (field (name "MANUFACTURER") "Panasonic"))
      (libsource (lib "Altium Content Vault") (part "RES"))
    )
    (comp (ref "TP17")
      (value "TPAD6R")
      (footprint "New footprint 1")
      (description "Test Point .6mm")
      (libsource (lib "Space Concordia") (part "TP"))
    )
    (comp (ref "TP18")
      (value "TPAD6R")
      (footprint "New footprint 1")
      (description "Test Point .6mm")
      (libsource (lib "Space Concordia") (part "TP"))
    )
    (comp (ref "TP21")
      (value "TPAD6R")
      (footprint "New footprint 1")
      (description "Test Point .6mm")
      (libsource (lib "Space Concordia") (part "TP"))
    )
    (comp (ref "TP88")
      (value "TPAD6R")
      (footprint "New footprint 1")
      (description "Test Point .6mm")
      (libsource (lib "Space Concordia") (part "TP"))
    )
    (comp (ref "TP89")
      (value "TPAD6R")
      (footprint "New footprint 1")
      (description "Test Point .6mm")
      (libsource (lib "Space Concordia") (part "TP"))
    )
    (comp (ref "U11")
      (value "SN74LVC1G07DCKR")
      (footprint "FP-DCK0005A-IPC_C")
      (description "IC BUFF/DVR NON-INVERT SC70-5")
      (libsource (lib "Altium Content Vault") (part "8ab337023d36144ede9cc3383aed264"))
    )
    (comp (ref "U12")
      (value "SN74LVC1G07DCKR")
      (footprint "FP-DCK0005A-IPC_C")
      (description "IC BUFF/DVR NON-INVERT SC70-5")
      (libsource (lib "Altium Content Vault") (part "8ab337023d36144ede9cc3383aed264"))
    )
    (comp (ref "U24")
      (value "LD1117S18TR")
      (footprint "SOT-223_M")
      (description "Fixed Low Drop Positive Voltage Regulator, 1.8V, 4-Pin SOT-223, Tape and Reel")
      (libsource (lib "Altium Content Vault") (part "PM-REG-LD1117-SOT4"))
    )
  )
  (nets
    (net (code "1") (name "/1V8_CAM0_PWDN") (class "Default")
      (node (ref "J1") (pin "114") (pinfunction "114_114") (pintype "passive"))
      (node (ref "R128") (pin "1") (pinfunction "1_1") (pintype "passive"))
    )
    (net (code "2") (name "/1V8_CAM1_PWDN") (class "Default")
      (node (ref "J1") (pin "120") (pinfunction "120_120") (pintype "passive"))
      (node (ref "R129") (pin "1") (pinfunction "1_1") (pintype "passive"))
    )
    (net (code "3") (name "/1V8_SMB_nALERT") (class "Default")
      (node (ref "R176") (pin "1") (pinfunction "1_1") (pintype "passive"))
      (node (ref "U12") (pin "2") (pinfunction "A_2") (pintype "input"))
    )
    (net (code "4") (name "/1V8_SPI1_MISO") (class "Default")
      (node (ref "D3") (pin "4") (pinfunction "IO3_4") (pintype "bidirectional"))
      (node (ref "D3") (pin "7") (pinfunction "NC_7") (pintype "passive"))
      (node (ref "J1") (pin "108") (pinfunction "108_108") (pintype "passive"))
      (node (ref "Q20") (pin "2") (pinfunction "S_2") (pintype "passive"))
      (node (ref "R268") (pin "1") (pinfunction "1_1") (pintype "passive"))
    )
    (net (code "5") (name "/1V8_SPI1_MOSI") (class "Default")
      (node (ref "D3") (pin "1") (pinfunction "IO1_1") (pintype "bidirectional"))
      (node (ref "D3") (pin "10") (pinfunction "NC_10") (pintype "passive"))
      (node (ref "J1") (pin "104") (pinfunction "104_104") (pintype "passive"))
      (node (ref "Q18") (pin "2") (pinfunction "S_2") (pintype "passive"))
      (node (ref "R234") (pin "1") (pinfunction "1_1") (pintype "passive"))
    )
    (net (code "6") (name "/1V8_SPI1_SCLK") (class "Default")
      (node (ref "D3") (pin "2") (pinfunction "IO2_2") (pintype "bidirectional"))
      (node (ref "D3") (pin "9") (pinfunction "NC_9") (pintype "passive"))
      (node (ref "J1") (pin "106") (pinfunction "106_106") (pintype "passive"))
      (node (ref "Q19") (pin "2") (pinfunction "S_2") (pintype "passive"))
      (node (ref "R265") (pin "1") (pinfunction "1_1") (pintype "passive"))
    )
    (net (code "7") (name "/1V8_SPI1_nCS_0") (class "Default")
      (node (ref "D3") (pin "5") (pinfunction "IO4_5") (pintype "bidirectional"))
      (node (ref "D3") (pin "6") (pinfunction "NC_6") (pintype "passive"))
      (node (ref "J1") (pin "110") (pinfunction "110_110") (pintype "passive"))
      (node (ref "Q21") (pin "2") (pinfunction "S_2") (pintype "passive"))
      (node (ref "R271") (pin "1") (pinfunction "1_1") (pintype "passive"))
    )
    (net (code "8") (name "/1V8_SPI1_nCS_1") (class "Default")
      (node (ref "J1") (pin "112") (pinfunction "112_112") (pintype "passive"))
      (node (ref "Q22") (pin "2") (pinfunction "S_2") (pintype "passive"))
      (node (ref "R274") (pin "1") (pinfunction "1_1") (pintype "passive"))
    )
    (net (code "9") (name "/CAM0_PWDN") (class "Default")
      (node (ref "Q9") (pin "6") (pinfunction "Drain1_6") (pintype "passive"))
    )
    (net (code "10") (name "/CAM1_PWDN") (class "Default")
      (node (ref "Q9") (pin "3") (pinfunction "Drain2_3") (pintype "passive"))
    )
    (net (code "11") (name "/CAM_I2C_SCL") (class "Default")
      (node (ref "D18") (pin "4") (pinfunction "IO3_4") (pintype "bidirectional"))
      (node (ref "D18") (pin "7") (pinfunction "NC_7") (pintype "passive"))
      (node (ref "J1") (pin "213") (pinfunction "213_213") (pintype "passive"))
    )
    (net (code "12") (name "/CAM_I2C_SDA") (class "Default")
      (node (ref "D18") (pin "5") (pinfunction "IO4_5") (pintype "bidirectional"))
      (node (ref "D18") (pin "6") (pinfunction "NC_6") (pintype "passive"))
      (node (ref "J1") (pin "215") (pinfunction "215_215") (pintype "passive"))
    )
    (net (code "13") (name "/CAN_RX") (class "Default")
      (node (ref "D17") (pin "1") (pinfunction "IO1_1") (pintype "bidirectional"))
      (node (ref "D17") (pin "10") (pinfunction "NC_10") (pintype "passive"))
      (node (ref "J1") (pin "143") (pinfunction "143_143") (pintype "passive"))
    )
    (net (code "14") (name "/CAN_TX") (class "Default")
      (node (ref "D17") (pin "2") (pinfunction "IO2_2") (pintype "bidirectional"))
      (node (ref "D17") (pin "9") (pinfunction "NC_9") (pintype "passive"))
      (node (ref "J1") (pin "145") (pinfunction "145_145") (pintype "passive"))
    )
    (net (code "15") (name "/CSI0_CLK_N") (class "Default")
      (node (ref "D6") (pin "2") (pinfunction "IO2_2") (pintype "bidirectional"))
      (node (ref "D6") (pin "9") (pinfunction "NC_9") (pintype "passive"))
      (node (ref "J1") (pin "10") (pinfunction "10_10") (pintype "passive"))
    )
    (net (code "16") (name "/CSI0_CLK_P") (class "Default")
      (node (ref "D6") (pin "1") (pinfunction "IO1_1") (pintype "bidirectional"))
      (node (ref "D6") (pin "10") (pinfunction "NC_10") (pintype "passive"))
      (node (ref "J1") (pin "12") (pinfunction "12_12") (pintype "passive"))
    )
    (net (code "17") (name "/CSI0_D0_N") (class "Default")
      (node (ref "D6") (pin "5") (pinfunction "IO4_5") (pintype "bidirectional"))
      (node (ref "D6") (pin "6") (pinfunction "NC_6") (pintype "passive"))
      (node (ref "J1") (pin "4") (pinfunction "4_4") (pintype "passive"))
    )
    (net (code "18") (name "/CSI0_D0_P") (class "Default")
      (node (ref "D6") (pin "4") (pinfunction "IO3_4") (pintype "bidirectional"))
      (node (ref "D6") (pin "7") (pinfunction "NC_7") (pintype "passive"))
      (node (ref "J1") (pin "6") (pinfunction "6_6") (pintype "passive"))
    )
    (net (code "19") (name "/CSI0_D1_N") (class "Default")
      (node (ref "R3") (pin "2") (pinfunction "2_2") (pintype "passive"))
    )
    (net (code "20") (name "/CSI0_D1_P") (class "Default")
      (node (ref "R4") (pin "2") (pinfunction "2_2") (pintype "passive"))
    )
    (net (code "21") (name "/CSI1_D0_N") (class "Default")
      (node (ref "R5") (pin "2") (pinfunction "2_2") (pintype "passive"))
    )
    (net (code "22") (name "/CSI1_D0_P") (class "Default")
      (node (ref "R6") (pin "2") (pinfunction "2_2") (pintype "passive"))
    )
    (net (code "23") (name "/CSI1_D1_N") (class "Default")
      (node (ref "D7") (pin "4") (pinfunction "IO3_4") (pintype "bidirectional"))
      (node (ref "D7") (pin "7") (pinfunction "NC_7") (pintype "passive"))
      (node (ref "J1") (pin "15") (pinfunction "15_15") (pintype "passive"))
    )
    (net (code "24") (name "/CSI1_D1_P") (class "Default")
      (node (ref "D7") (pin "5") (pinfunction "IO4_5") (pintype "bidirectional"))
      (node (ref "D7") (pin "6") (pinfunction "NC_6") (pintype "passive"))
      (node (ref "J1") (pin "17") (pinfunction "17_17") (pintype "passive"))
    )
    (net (code "25") (name "/CSI2_CLK_N") (class "Default")
      (node (ref "D19") (pin "1") (pinfunction "IO1_1") (pintype "bidirectional"))
      (node (ref "D19") (pin "10") (pinfunction "NC_10") (pintype "passive"))
      (node (ref "J1") (pin "28") (pinfunction "28_28") (pintype "passive"))
    )
    (net (code "26") (name "/CSI2_CLK_P") (class "Default")
      (node (ref "D19") (pin "2") (pinfunction "IO2_2") (pintype "bidirectional"))
      (node (ref "D19") (pin "9") (pinfunction "NC_9") (pintype "passive"))
      (node (ref "J1") (pin "30") (pinfunction "30_30") (pintype "passive"))
    )
    (net (code "27") (name "/CSI2_D0_N") (class "Default")
      (node (ref "D13") (pin "4") (pinfunction "IO3_4") (pintype "bidirectional"))
      (node (ref "D13") (pin "7") (pinfunction "NC_7") (pintype "passive"))
      (node (ref "J1") (pin "22") (pinfunction "22_22") (pintype "passive"))
    )
    (net (code "28") (name "/CSI2_D0_P") (class "Default")
      (node (ref "D13") (pin "5") (pinfunction "IO4_5") (pintype "bidirectional"))
      (node (ref "D13") (pin "6") (pinfunction "NC_6") (pintype "passive"))
      (node (ref "J1") (pin "24") (pinfunction "24_24") (pintype "passive"))
    )
    (net (code "29") (name "/CSI2_D1_N") (class "Default")
      (node (ref "D19") (pin "4") (pinfunction "IO3_4") (pintype "bidirectional"))
      (node (ref "D19") (pin "7") (pinfunction "NC_7") (pintype "passive"))
      (node (ref "J1") (pin "34") (pinfunction "34_34") (pintype "passive"))
    )
    (net (code "30") (name "/CSI2_D1_P") (class "Default")
      (node (ref "D19") (pin "5") (pinfunction "IO4_5") (pintype "bidirectional"))
      (node (ref "D19") (pin "6") (pinfunction "NC_6") (pintype "passive"))
      (node (ref "J1") (pin "36") (pinfunction "36_36") (pintype "passive"))
    )
    (net (code "31") (name "/CSI3_D0_N") (class "Default")
      (node (ref "D14") (pin "1") (pinfunction "IO1_1") (pintype "bidirectional"))
      (node (ref "D14") (pin "10") (pinfunction "NC_10") (pintype "passive"))
      (node (ref "J1") (pin "21") (pinfunction "21_21") (pintype "passive"))
    )
    (net (code "32") (name "/CSI3_D0_P") (class "Default")
      (node (ref "D14") (pin "2") (pinfunction "IO2_2") (pintype "bidirectional"))
      (node (ref "D14") (pin "9") (pinfunction "NC_9") (pintype "passive"))
      (node (ref "J1") (pin "23") (pinfunction "23_23") (pintype "passive"))
    )
    (net (code "33") (name "/CSI3_D1_N") (class "Default")
      (node (ref "D14") (pin "4") (pinfunction "IO3_4") (pintype "bidirectional"))
      (node (ref "D14") (pin "7") (pinfunction "NC_7") (pintype "passive"))
      (node (ref "J1") (pin "33") (pinfunction "33_33") (pintype "passive"))
    )
    (net (code "34") (name "/CSI3_D1_P") (class "Default")
      (node (ref "D14") (pin "5") (pinfunction "IO4_5") (pintype "bidirectional"))
      (node (ref "D14") (pin "6") (pinfunction "NC_6") (pintype "passive"))
      (node (ref "J1") (pin "35") (pinfunction "35_35") (pintype "passive"))
    )
    (net (code "35") (name "/DEBUG_RXD") (class "Default")
      (node (ref "R64") (pin "2") (pinfunction "2_2") (pintype "passive"))
    )
    (net (code "36") (name "/DEBUG_TXD") (class "Default")
      (node (ref "R122") (pin "2") (pinfunction "2_2") (pintype "passive"))
    )
    (net (code "37") (name "/DP1_AUX_N") (class "Default")
      (node (ref "D20") (pin "4") (pinfunction "IO3_4") (pintype "bidirectional"))
      (node (ref "D20") (pin "7") (pinfunction "NC_7") (pintype "passive"))
      (node (ref "J1") (pin "98") (pinfunction "98_98") (pintype "passive"))
    )
    (net (code "38") (name "/DP1_AUX_P") (class "Default")
      (node (ref "D20") (pin "5") (pinfunction "IO4_5") (pintype "bidirectional"))
      (node (ref "D20") (pin "6") (pinfunction "NC_6") (pintype "passive"))
      (node (ref "J1") (pin "100") (pinfunction "100_100") (pintype "passive"))
    )
    (net (code "39") (name "/DP1_HPD") (class "Default")
      (node (ref "D20") (pin "2") (pinfunction "IO2_2") (pintype "bidirectional"))
      (node (ref "D20") (pin "9") (pinfunction "NC_9") (pintype "passive"))
      (node (ref "J1") (pin "96") (pinfunction "96_96") (pintype "passive"))
    )
    (net (code "40") (name "/DP1_TXD0_N") (class "Default")
      (node (ref "D8") (pin "1") (pinfunction "IO1_1") (pintype "bidirectional"))
      (node (ref "D8") (pin "10") (pinfunction "NC_10") (pintype "passive"))
      (node (ref "J1") (pin "63") (pinfunction "63_63") (pintype "passive"))
    )
    (net (code "41") (name "/DP1_TXD0_P") (class "Default")
      (node (ref "D8") (pin "2") (pinfunction "IO2_2") (pintype "bidirectional"))
      (node (ref "D8") (pin "9") (pinfunction "NC_9") (pintype "passive"))
      (node (ref "J1") (pin "65") (pinfunction "65_65") (pintype "passive"))
    )
    (net (code "42") (name "/DP1_TXD1_N") (class "Default")
      (node (ref "D8") (pin "4") (pinfunction "IO3_4") (pintype "bidirectional"))
      (node (ref "D8") (pin "7") (pinfunction "NC_7") (pintype "passive"))
      (node (ref "J1") (pin "69") (pinfunction "69_69") (pintype "passive"))
    )
    (net (code "43") (name "/DP1_TXD1_P") (class "Default")
      (node (ref "D8") (pin "5") (pinfunction "IO4_5") (pintype "bidirectional"))
      (node (ref "D8") (pin "6") (pinfunction "NC_6") (pintype "passive"))
      (node (ref "J1") (pin "71") (pinfunction "71_71") (pintype "passive"))
    )
    (net (code "44") (name "/DP1_TXD2_N") (class "Default")
      (node (ref "D15") (pin "1") (pinfunction "IO1_1") (pintype "bidirectional"))
      (node (ref "D15") (pin "10") (pinfunction "NC_10") (pintype "passive"))
      (node (ref "J1") (pin "75") (pinfunction "75_75") (pintype "passive"))
    )
    (net (code "45") (name "/DP1_TXD2_P") (class "Default")
      (node (ref "D15") (pin "2") (pinfunction "IO2_2") (pintype "bidirectional"))
      (node (ref "D15") (pin "9") (pinfunction "NC_9") (pintype "passive"))
      (node (ref "J1") (pin "77") (pinfunction "77_77") (pintype "passive"))
    )
    (net (code "46") (name "/DP1_TXD3_N") (class "Default")
      (node (ref "D15") (pin "4") (pinfunction "IO3_4") (pintype "bidirectional"))
      (node (ref "D15") (pin "7") (pinfunction "NC_7") (pintype "passive"))
      (node (ref "J1") (pin "81") (pinfunction "81_81") (pintype "passive"))
    )
    (net (code "47") (name "/DP1_TXD3_P") (class "Default")
      (node (ref "D15") (pin "5") (pinfunction "IO4_5") (pintype "bidirectional"))
      (node (ref "D15") (pin "6") (pinfunction "NC_6") (pintype "passive"))
      (node (ref "J1") (pin "83") (pinfunction "83_83") (pintype "passive"))
    )
    (net (code "48") (name "/DP_HDMI_CEC") (class "Default")
      (node (ref "D20") (pin "1") (pinfunction "IO1_1") (pintype "bidirectional"))
      (node (ref "D20") (pin "10") (pinfunction "NC_10") (pintype "passive"))
      (node (ref "J1") (pin "94") (pinfunction "94_94") (pintype "passive"))
    )
    (net (code "49") (name "/GBE_LED_ACT") (class "Default")
      (node (ref "J1") (pin "194") (pinfunction "194_194") (pintype "passive"))
    )
    (net (code "50") (name "/GBE_LED_LINK") (class "Default")
      (node (ref "J1") (pin "188") (pinfunction "188_188") (pintype "passive"))
    )
    (net (code "51") (name "/GBE_MDI0_N") (class "Default")
      (node (ref "D5") (pin "1") (pinfunction "IO1_1") (pintype "bidirectional"))
      (node (ref "D5") (pin "10") (pinfunction "NC_10") (pintype "passive"))
      (node (ref "J1") (pin "184") (pinfunction "184_184") (pintype "passive"))
    )
    (net (code "52") (name "/GBE_MDI0_P") (class "Default")
      (node (ref "D5") (pin "2") (pinfunction "IO2_2") (pintype "bidirectional"))
      (node (ref "D5") (pin "9") (pinfunction "NC_9") (pintype "passive"))
      (node (ref "J1") (pin "186") (pinfunction "186_186") (pintype "passive"))
    )
    (net (code "53") (name "/GBE_MDI1_N") (class "Default")
      (node (ref "D5") (pin "4") (pinfunction "IO3_4") (pintype "bidirectional"))
      (node (ref "D5") (pin "7") (pinfunction "NC_7") (pintype "passive"))
      (node (ref "J1") (pin "190") (pinfunction "190_190") (pintype "passive"))
    )
    (net (code "54") (name "/GBE_MDI1_P") (class "Default")
      (node (ref "D5") (pin "5") (pinfunction "IO4_5") (pintype "bidirectional"))
      (node (ref "D5") (pin "6") (pinfunction "NC_6") (pintype "passive"))
      (node (ref "J1") (pin "192") (pinfunction "192_192") (pintype "passive"))
    )
    (net (code "55") (name "/GBE_MDI2_N") (class "Default")
      (node (ref "D12") (pin "1") (pinfunction "IO1_1") (pintype "bidirectional"))
      (node (ref "D12") (pin "10") (pinfunction "NC_10") (pintype "passive"))
      (node (ref "J1") (pin "196") (pinfunction "196_196") (pintype "passive"))
    )
    (net (code "56") (name "/GBE_MDI2_P") (class "Default")
      (node (ref "D12") (pin "2") (pinfunction "IO2_2") (pintype "bidirectional"))
      (node (ref "D12") (pin "9") (pinfunction "NC_9") (pintype "passive"))
      (node (ref "J1") (pin "198") (pinfunction "198_198") (pintype "passive"))
    )
    (net (code "57") (name "/GBE_MDI3_N") (class "Default")
      (node (ref "D12") (pin "4") (pinfunction "IO3_4") (pintype "bidirectional"))
      (node (ref "D12") (pin "7") (pinfunction "NC_7") (pintype "passive"))
      (node (ref "J1") (pin "202") (pinfunction "202_202") (pintype "passive"))
    )
    (net (code "58") (name "/GBE_MDI3_P") (class "Default")
      (node (ref "D12") (pin "5") (pinfunction "IO4_5") (pintype "bidirectional"))
      (node (ref "D12") (pin "6") (pinfunction "NC_6") (pintype "passive"))
      (node (ref "J1") (pin "204") (pinfunction "204_204") (pintype "passive"))
    )
    (net (code "59") (name "/GPIO08_FAN_TACH") (class "Default")
      (node (ref "J1") (pin "208") (pinfunction "208_208") (pintype "passive"))
    )
    (net (code "60") (name "/GPIO10_nSMB_ALERT") (class "Default")
      (node (ref "J1") (pin "212") (pinfunction "212_212") (pintype "passive"))
      (node (ref "R175") (pin "1") (pinfunction "1_1") (pintype "passive"))
      (node (ref "U12") (pin "4") (pinfunction "Y_4") (pintype "output"))
    )
    (net (code "61") (name "/GPIO14_FAN_PWM") (class "Default")
      (node (ref "J1") (pin "230") (pinfunction "230_230") (pintype "passive"))
    )
    (net (code "62") (name "/GPIO_01") (class "Default")
      (node (ref "J1") (pin "118") (pinfunction "118_118") (pintype "passive"))
    )
    (net (code "63") (name "/GPIO_02") (class "Default")
      (node (ref "J1") (pin "124") (pinfunction "124_124") (pintype "passive"))
    )
    (net (code "64") (name "/GPIO_03") (class "Default")
      (node (ref "J1") (pin "126") (pinfunction "126_126") (pintype "passive"))
    )
    (net (code "65") (name "/GPIO_04") (class "Default")
      (node (ref "J1") (pin "127") (pinfunction "127_127") (pintype "passive"))
    )
    (net (code "66") (name "/GPIO_05") (class "Default")
      (node (ref "J1") (pin "128") (pinfunction "128_128") (pintype "passive"))
    )
    (net (code "67") (name "/GPIO_06") (class "Default")
      (node (ref "J1") (pin "130") (pinfunction "130_130") (pintype "passive"))
    )
    (net (code "68") (name "/GPIO_07") (class "Default")
      (node (ref "J1") (pin "206") (pinfunction "206_206") (pintype "passive"))
    )
    (net (code "69") (name "/GPIO_09") (class "Default")
      (node (ref "J1") (pin "211") (pinfunction "211_211") (pintype "passive"))
    )
    (net (code "70") (name "/GPIO_11") (class "Default")
      (node (ref "J1") (pin "216") (pinfunction "216_216") (pintype "passive"))
    )
    (net (code "71") (name "/GPIO_12") (class "Default")
      (node (ref "J1") (pin "218") (pinfunction "218_218") (pintype "passive"))
    )
    (net (code "72") (name "/GPIO_13") (class "Default")
      (node (ref "J1") (pin "228") (pinfunction "228_228") (pintype "passive"))
    )
    (net (code "73") (name "/I2C0_SCL") (class "Default")
      (node (ref "D2") (pin "4") (pinfunction "IO3_4") (pintype "bidirectional"))
      (node (ref "D2") (pin "7") (pinfunction "NC_7") (pintype "passive"))
      (node (ref "J1") (pin "185") (pinfunction "185_185") (pintype "passive"))
    )
    (net (code "74") (name "/I2C0_SDA") (class "Default")
      (node (ref "D2") (pin "5") (pinfunction "IO4_5") (pintype "bidirectional"))
      (node (ref "D2") (pin "6") (pinfunction "NC_6") (pintype "passive"))
      (node (ref "J1") (pin "187") (pinfunction "187_187") (pintype "passive"))
    )
    (net (code "75") (name "/I2C1_SCL") (class "Default")
      (node (ref "J1") (pin "189") (pinfunction "189_189") (pintype "passive"))
    )
    (net (code "76") (name "/I2C1_SDA") (class "Default")
      (node (ref "J1") (pin "191") (pinfunction "191_191") (pintype "passive"))
    )
    (net (code "77") (name "/I2S0_DIN") (class "Default")
      (node (ref "D4") (pin "2") (pinfunction "IO2_2") (pintype "bidirectional"))
      (node (ref "D4") (pin "9") (pinfunction "NC_9") (pintype "passive"))
      (node (ref "J1") (pin "195") (pinfunction "195_195") (pintype "passive"))
      (node (ref "TP17") (pin "1") (pinfunction "TP_1") (pintype "passive"))
    )
    (net (code "78") (name "/I2S0_DOUT") (class "Default")
      (node (ref "D4") (pin "1") (pinfunction "IO1_1") (pintype "bidirectional"))
      (node (ref "D4") (pin "10") (pinfunction "NC_10") (pintype "passive"))
      (node (ref "J1") (pin "193") (pinfunction "193_193") (pintype "passive"))
      (node (ref "TP21") (pin "1") (pinfunction "TP_1") (pintype "passive"))
    )
    (net (code "79") (name "/I2S0_FS") (class "Default")
      (node (ref "D4") (pin "4") (pinfunction "IO3_4") (pintype "bidirectional"))
      (node (ref "D4") (pin "7") (pinfunction "NC_7") (pintype "passive"))
      (node (ref "J1") (pin "197") (pinfunction "197_197") (pintype "passive"))
      (node (ref "TP88") (pin "1") (pinfunction "TP_1") (pintype "passive"))
    )
    (net (code "80") (name "/I2S0_SCLK") (class "Default")
      (node (ref "D4") (pin "5") (pinfunction "IO4_5") (pintype "bidirectional"))
      (node (ref "D4") (pin "6") (pinfunction "NC_6") (pintype "passive"))
      (node (ref "J1") (pin "199") (pinfunction "199_199") (pintype "passive"))
      (node (ref "TP89") (pin "1") (pinfunction "TP_1") (pintype "passive"))
    )
    (net (code "81") (name "/MODULE_ID") (class "Default")
      (node (ref "J1") (pin "217") (pinfunction "217_217") (pintype "passive"))
      (node (ref "R127") (pin "1") (pinfunction "1_1") (pintype "passive"))
    )
    (net (code "82") (name "/PCIE0_CLK_N") (class "Default")
      (node (ref "D1") (pin "1") (pinfunction "IO1_1") (pintype "bidirectional"))
      (node (ref "D1") (pin "10") (pinfunction "NC_10") (pintype "passive"))
      (node (ref "J1") (pin "160") (pinfunction "160_160") (pintype "passive"))
    )
    (net (code "83") (name "/PCIE0_CLK_P") (class "Default")
      (node (ref "D1") (pin "2") (pinfunction "IO2_2") (pintype "bidirectional"))
      (node (ref "D1") (pin "9") (pinfunction "NC_9") (pintype "passive"))
      (node (ref "J1") (pin "162") (pinfunction "162_162") (pintype "passive"))
    )
    (net (code "84") (name "/PCIE0_RX0_N") (class "Default")
      (node (ref "D10") (pin "1") (pinfunction "IO1_1") (pintype "bidirectional"))
      (node (ref "D10") (pin "10") (pinfunction "NC_10") (pintype "passive"))
      (node (ref "J1") (pin "131") (pinfunction "131_131") (pintype "passive"))
    )
    (net (code "85") (name "/PCIE0_RX0_P") (class "Default")
      (node (ref "D10") (pin "2") (pinfunction "IO2_2") (pintype "bidirectional"))
      (node (ref "D10") (pin "9") (pinfunction "NC_9") (pintype "passive"))
      (node (ref "J1") (pin "133") (pinfunction "133_133") (pintype "passive"))
    )
    (net (code "86") (name "/PCIE0_RX1_N") (class "Default")
      (node (ref "D10") (pin "4") (pinfunction "IO3_4") (pintype "bidirectional"))
      (node (ref "D10") (pin "7") (pinfunction "NC_7") (pintype "passive"))
      (node (ref "J1") (pin "137") (pinfunction "137_137") (pintype "passive"))
    )
    (net (code "87") (name "/PCIE0_RX1_P") (class "Default")
      (node (ref "D10") (pin "5") (pinfunction "IO4_5") (pintype "bidirectional"))
      (node (ref "D10") (pin "6") (pinfunction "NC_6") (pintype "passive"))
      (node (ref "J1") (pin "139") (pinfunction "139_139") (pintype "passive"))
    )
    (net (code "88") (name "/PCIE0_RX2_N") (class "Default")
      (node (ref "D17") (pin "4") (pinfunction "IO3_4") (pintype "bidirectional"))
      (node (ref "D17") (pin "7") (pinfunction "NC_7") (pintype "passive"))
      (node (ref "J1") (pin "149") (pinfunction "149_149") (pintype "passive"))
    )
    (net (code "89") (name "/PCIE0_RX2_P") (class "Default")
      (node (ref "D17") (pin "5") (pinfunction "IO4_5") (pintype "bidirectional"))
      (node (ref "D17") (pin "6") (pinfunction "NC_6") (pintype "passive"))
      (node (ref "J1") (pin "151") (pinfunction "151_151") (pintype "passive"))
    )
    (net (code "90") (name "/PCIE0_RX3_N") (class "Default")
      (node (ref "D16") (pin "1") (pinfunction "IO1_1") (pintype "bidirectional"))
      (node (ref "D16") (pin "10") (pinfunction "NC_10") (pintype "passive"))
      (node (ref "J1") (pin "155") (pinfunction "155_155") (pintype "passive"))
    )
    (net (code "91") (name "/PCIE0_RX3_P") (class "Default")
      (node (ref "D16") (pin "2") (pinfunction "IO2_2") (pintype "bidirectional"))
      (node (ref "D16") (pin "9") (pinfunction "NC_9") (pintype "passive"))
      (node (ref "J1") (pin "157") (pinfunction "157_157") (pintype "passive"))
    )
    (net (code "92") (name "/PCIE0_TX0_N") (class "Default")
      (node (ref "D21") (pin "1") (pinfunction "IO1_1") (pintype "bidirectional"))
      (node (ref "D21") (pin "10") (pinfunction "NC_10") (pintype "passive"))
      (node (ref "J1") (pin "134") (pinfunction "134_134") (pintype "passive"))
    )
    (net (code "93") (name "/PCIE0_TX0_P") (class "Default")
      (node (ref "D21") (pin "2") (pinfunction "IO2_2") (pintype "bidirectional"))
      (node (ref "D21") (pin "9") (pinfunction "NC_9") (pintype "passive"))
      (node (ref "J1") (pin "136") (pinfunction "136_136") (pintype "passive"))
    )
    (net (code "94") (name "/PCIE0_TX1_N") (class "Default")
      (node (ref "D21") (pin "4") (pinfunction "IO3_4") (pintype "bidirectional"))
      (node (ref "D21") (pin "7") (pinfunction "NC_7") (pintype "passive"))
      (node (ref "J1") (pin "140") (pinfunction "140_140") (pintype "passive"))
    )
    (net (code "95") (name "/PCIE0_TX1_P") (class "Default")
      (node (ref "D21") (pin "5") (pinfunction "IO4_5") (pintype "bidirectional"))
      (node (ref "D21") (pin "6") (pinfunction "NC_6") (pintype "passive"))
      (node (ref "J1") (pin "142") (pinfunction "142_142") (pintype "passive"))
    )
    (net (code "96") (name "/PCIE0_TX2_N") (class "Default")
      (node (ref "D11") (pin "1") (pinfunction "IO1_1") (pintype "bidirectional"))
      (node (ref "D11") (pin "10") (pinfunction "NC_10") (pintype "passive"))
      (node (ref "J1") (pin "148") (pinfunction "148_148") (pintype "passive"))
    )
    (net (code "97") (name "/PCIE0_TX2_P") (class "Default")
      (node (ref "D11") (pin "2") (pinfunction "IO2_2") (pintype "bidirectional"))
      (node (ref "D11") (pin "9") (pinfunction "NC_9") (pintype "passive"))
      (node (ref "J1") (pin "150") (pinfunction "150_150") (pintype "passive"))
    )
    (net (code "98") (name "/PCIE0_TX3_N") (class "Default")
      (node (ref "D11") (pin "4") (pinfunction "IO3_4") (pintype "bidirectional"))
      (node (ref "D11") (pin "7") (pinfunction "NC_7") (pintype "passive"))
      (node (ref "J1") (pin "154") (pinfunction "154_154") (pintype "passive"))
    )
    (net (code "99") (name "/PCIE0_TX3_P") (class "Default")
      (node (ref "D11") (pin "5") (pinfunction "IO4_5") (pintype "bidirectional"))
      (node (ref "D11") (pin "6") (pinfunction "NC_6") (pintype "passive"))
      (node (ref "J1") (pin "156") (pinfunction "156_156") (pintype "passive"))
    )
    (net (code "100") (name "/PCIE0_nCLKREQ") (class "Default")
      (node (ref "J1") (pin "180") (pinfunction "180_180") (pintype "passive"))
    )
    (net (code "101") (name "/PCIE0_nRST") (class "Default")
      (node (ref "D2") (pin "2") (pinfunction "IO2_2") (pintype "bidirectional"))
      (node (ref "D2") (pin "9") (pinfunction "NC_9") (pintype "passive"))
      (node (ref "J1") (pin "181") (pinfunction "181_181") (pintype "passive"))
    )
    (net (code "102") (name "/PCIE_32K_CLK") (class "Default")
      (node (ref "R174") (pin "1") (pinfunction "1_1") (pintype "passive"))
      (node (ref "U11") (pin "4") (pinfunction "Y_4") (pintype "output"))
    )
    (net (code "103") (name "/PCIE_WAKE") (class "Default")
      (node (ref "D2") (pin "1") (pinfunction "IO1_1") (pintype "bidirectional"))
      (node (ref "D2") (pin "10") (pinfunction "NC_10") (pintype "passive"))
      (node (ref "J1") (pin "179") (pinfunction "179_179") (pintype "passive"))
    )
    (net (code "104") (name "/PMIC_BBAT") (class "Default")
      (node (ref "J1") (pin "235") (pinfunction "235_235") (pintype "passive"))
      (node (ref "TP18") (pin "1") (pinfunction "TP_1") (pintype "passive"))
    )
    (net (code "105") (name "/POWER_EN") (class "Default")
      (node (ref "J1") (pin "237") (pinfunction "237_237") (pintype "passive"))
    )
    (net (code "106") (name "/PRE_CSI0_D1_N") (class "Default")
      (node (ref "D13") (pin "1") (pinfunction "IO1_1") (pintype "bidirectional"))
      (node (ref "D13") (pin "10") (pinfunction "NC_10") (pintype "passive"))
      (node (ref "J1") (pin "16") (pinfunction "16_16") (pintype "passive"))
      (node (ref "R3") (pin "1") (pinfunction "1_1") (pintype "passive"))
    )
    (net (code "107") (name "/PRE_CSI0_D1_P") (class "Default")
      (node (ref "D13") (pin "2") (pinfunction "IO2_2") (pintype "bidirectional"))
      (node (ref "D13") (pin "9") (pinfunction "NC_9") (pintype "passive"))
      (node (ref "J1") (pin "18") (pinfunction "18_18") (pintype "passive"))
      (node (ref "R4") (pin "1") (pinfunction "1_1") (pintype "passive"))
    )
    (net (code "108") (name "/PRE_CSI1_D0_N") (class "Default")
      (node (ref "D7") (pin "1") (pinfunction "IO1_1") (pintype "bidirectional"))
      (node (ref "D7") (pin "10") (pinfunction "NC_10") (pintype "passive"))
      (node (ref "J1") (pin "3") (pinfunction "3_3") (pintype "passive"))
      (node (ref "R5") (pin "1") (pinfunction "1_1") (pintype "passive"))
    )
    (net (code "109") (name "/PRE_CSI1_D0_P") (class "Default")
      (node (ref "D7") (pin "2") (pinfunction "IO2_2") (pintype "bidirectional"))
      (node (ref "D7") (pin "9") (pinfunction "NC_9") (pintype "passive"))
      (node (ref "J1") (pin "5") (pinfunction "5_5") (pintype "passive"))
      (node (ref "R6") (pin "1") (pinfunction "1_1") (pintype "passive"))
    )
    (net (code "110") (name "/PRE_PCIE_32K_CLK") (class "Default")
      (node (ref "J1") (pin "210") (pinfunction "210_210") (pintype "passive"))
      (node (ref "U11") (pin "2") (pinfunction "A_2") (pintype "input"))
    )
    (net (code "111") (name "/SLEEP{slash}nWAKE") (class "Default")
      (node (ref "J1") (pin "240") (pinfunction "240_240") (pintype "passive"))
      (node (ref "R316") (pin "2") (pinfunction "2_2") (pintype "passive"))
    )
    (net (code "112") (name "/SPI1_MISO") (class "Default")
      (node (ref "R270") (pin "2") (pinfunction "2_2") (pintype "passive"))
    )
    (net (code "113") (name "/SPI1_MOSI") (class "Default")
      (node (ref "R264") (pin "2") (pinfunction "2_2") (pintype "passive"))
    )
    (net (code "114") (name "/SPI1_SCLK") (class "Default")
      (node (ref "R267") (pin "2") (pinfunction "2_2") (pintype "passive"))
    )
    (net (code "115") (name "/SPI1_nCS_0") (class "Default")
      (node (ref "R273") (pin "2") (pinfunction "2_2") (pintype "passive"))
    )
    (net (code "116") (name "/SPI1_nCS_1") (class "Default")
      (node (ref "R276") (pin "2") (pinfunction "2_2") (pintype "passive"))
    )
    (net (code "117") (name "/UART2_RXD") (class "Default")
      (node (ref "J1") (pin "238") (pinfunction "238_238") (pintype "passive"))
      (node (ref "Q7") (pin "2") (pinfunction "S_2") (pintype "passive"))
      (node (ref "R62") (pin "1") (pinfunction "1_1") (pintype "passive"))
    )
    (net (code "118") (name "/UART2_TXD") (class "Default")
      (node (ref "J1") (pin "236") (pinfunction "236_236") (pintype "passive"))
      (node (ref "Q8") (pin "2") (pinfunction "S_2") (pintype "passive"))
      (node (ref "R92") (pin "1") (pinfunction "1_1") (pintype "passive"))
    )
    (net (code "119") (name "/USB0_D_N") (class "Default")
      (node (ref "D9") (pin "1") (pinfunction "IO1_1") (pintype "bidirectional"))
      (node (ref "D9") (pin "10") (pinfunction "NC_10") (pintype "passive"))
      (node (ref "J1") (pin "109") (pinfunction "109_109") (pintype "passive"))
    )
    (net (code "120") (name "/USB0_D_P") (class "Default")
      (node (ref "D9") (pin "2") (pinfunction "IO2_2") (pintype "bidirectional"))
      (node (ref "D9") (pin "9") (pinfunction "NC_9") (pintype "passive"))
      (node (ref "J1") (pin "111") (pinfunction "111_111") (pintype "passive"))
    )
    (net (code "121") (name "/USB1_D_N") (class "Default")
      (node (ref "D9") (pin "4") (pinfunction "IO3_4") (pintype "bidirectional"))
      (node (ref "D9") (pin "7") (pinfunction "NC_7") (pintype "passive"))
      (node (ref "J1") (pin "115") (pinfunction "115_115") (pintype "passive"))
    )
    (net (code "122") (name "/USB1_D_P") (class "Default")
      (node (ref "D9") (pin "5") (pinfunction "IO4_5") (pintype "bidirectional"))
      (node (ref "D9") (pin "6") (pinfunction "NC_6") (pintype "passive"))
      (node (ref "J1") (pin "117") (pinfunction "117_117") (pintype "passive"))
    )
    (net (code "123") (name "/USBSS0_RX_N") (class "Default")
      (node (ref "D16") (pin "4") (pinfunction "IO3_4") (pintype "bidirectional"))
      (node (ref "D16") (pin "7") (pinfunction "NC_7") (pintype "passive"))
      (node (ref "J1") (pin "161") (pinfunction "161_161") (pintype "passive"))
    )
    (net (code "124") (name "/USBSS0_RX_P") (class "Default")
      (node (ref "D16") (pin "5") (pinfunction "IO4_5") (pintype "bidirectional"))
      (node (ref "D16") (pin "6") (pinfunction "NC_6") (pintype "passive"))
      (node (ref "J1") (pin "163") (pinfunction "163_163") (pintype "passive"))
    )
    (net (code "125") (name "/USBSS0_TX_N") (class "Default")
      (node (ref "D1") (pin "4") (pinfunction "IO3_4") (pintype "bidirectional"))
      (node (ref "D1") (pin "7") (pinfunction "NC_7") (pintype "passive"))
      (node (ref "J1") (pin "166") (pinfunction "166_166") (pintype "passive"))
    )
    (net (code "126") (name "/USBSS0_TX_P") (class "Default")
      (node (ref "D1") (pin "5") (pinfunction "IO4_5") (pintype "bidirectional"))
      (node (ref "D1") (pin "6") (pinfunction "NC_6") (pintype "passive"))
      (node (ref "J1") (pin "168") (pinfunction "168_168") (pintype "passive"))
    )
    (net (code "127") (name "/VBUS_DETECT") (class "Default")
      (node (ref "J1") (pin "87") (pinfunction "87_87") (pintype "passive"))
    )
    (net (code "128") (name "/nFORCE_RECOVERY") (class "Default")
      (node (ref "J1") (pin "214") (pinfunction "214_214") (pintype "passive"))
      (node (ref "J17") (pin "1") (pinfunction "1_1") (pintype "passive"))
      (node (ref "R355") (pin "1") (pinfunction "1_1") (pintype "passive"))
    )
    (net (code "129") (name "/nMOD_SLEEP") (class "Default")
      (node (ref "J1") (pin "178") (pinfunction "178_178") (pintype "passive"))
    )
    (net (code "130") (name "/nSHUTDOWN_REQ") (class "Default")
      (node (ref "J1") (pin "233") (pinfunction "233_233") (pintype "passive"))
    )
    (net (code "131") (name "/nSYS_RESET") (class "Default")
      (node (ref "J1") (pin "239") (pinfunction "239_239") (pintype "passive"))
    )
    (net (code "132") (name "2V_AUX") (class "Default")
      (node (ref "C214") (pin "2") (pinfunction "2_2") (pintype "passive"))
      (node (ref "U24") (pin "3") (pinfunction "VIN_3") (pintype "power_in"))
    )
    (net (code "133") (name "3V3_AUX") (class "Default")
      (node (ref "R174") (pin "2") (pinfunction "2_2") (pintype "passive"))
    )
    (net (code "134") (name "5V_MAIN") (class "Default")
      (node (ref "J1") (pin "251") (pinfunction "251_251") (pintype "passive"))
      (node (ref "J1") (pin "252") (pinfunction "252_252") (pintype "passive"))
      (node (ref "J1") (pin "253") (pinfunction "253_253") (pintype "passive"))
      (node (ref "J1") (pin "254") (pinfunction "254_254") (pintype "passive"))
      (node (ref "J1") (pin "255") (pinfunction "255_255") (pintype "passive"))
      (node (ref "J1") (pin "256") (pinfunction "256_256") (pintype "passive"))
      (node (ref "J1") (pin "257") (pinfunction "257_257") (pintype "passive"))
      (node (ref "J1") (pin "258") (pinfunction "258_258") (pintype "passive"))
      (node (ref "J1") (pin "259") (pinfunction "259_259") (pintype "passive"))
      (node (ref "J1") (pin "260") (pinfunction "260_260") (pintype "passive"))
      (node (ref "R118") (pin "2") (pinfunction "2_2") (pintype "passive"))
      (node (ref "R235") (pin "2") (pinfunction "2_2") (pintype "passive"))
      (node (ref "R266") (pin "2") (pinfunction "2_2") (pintype "passive"))
      (node (ref "R269") (pin "2") (pinfunction "2_2") (pintype "passive"))
      (node (ref "R272") (pin "2") (pinfunction "2_2") (pintype "passive"))
      (node (ref "R275") (pin "2") (pinfunction "2_2") (pintype "passive"))
      (node (ref "R63") (pin "2") (pinfunction "2_2") (pintype "passive"))
    )
    (net (code "135") (name "GND") (class "Default")
      (node (ref "C103") (pin "2") (pinfunction "2_2") (pintype "passive"))
      (node (ref "C116") (pin "2") (pinfunction "2_2") (pintype "passive"))
      (node (ref "C213") (pin "2") (pinfunction "2_2") (pintype "passive"))
      (node (ref "C214") (pin "1") (pinfunction "1_1") (pintype "passive"))
      (node (ref "D1") (pin "3") (pinfunction "GND_3") (pintype "power_in"))
      (node (ref "D1") (pin "8") (pinfunction "GND_8") (pintype "power_in"))
      (node (ref "D10") (pin "3") (pinfunction "GND_3") (pintype "power_in"))
      (node (ref "D10") (pin "8") (pinfunction "GND_8") (pintype "power_in"))
      (node (ref "D11") (pin "3") (pinfunction "GND_3") (pintype "power_in"))
      (node (ref "D11") (pin "8") (pinfunction "GND_8") (pintype "power_in"))
      (node (ref "D12") (pin "3") (pinfunction "GND_3") (pintype "power_in"))
      (node (ref "D12") (pin "8") (pinfunction "GND_8") (pintype "power_in"))
      (node (ref "D13") (pin "3") (pinfunction "GND_3") (pintype "power_in"))
      (node (ref "D13") (pin "8") (pinfunction "GND_8") (pintype "power_in"))
      (node (ref "D14") (pin "3") (pinfunction "GND_3") (pintype "power_in"))
      (node (ref "D14") (pin "8") (pinfunction "GND_8") (pintype "power_in"))
      (node (ref "D15") (pin "3") (pinfunction "GND_3") (pintype "power_in"))
      (node (ref "D15") (pin "8") (pinfunction "GND_8") (pintype "power_in"))
      (node (ref "D16") (pin "3") (pinfunction "GND_3") (pintype "power_in"))
      (node (ref "D16") (pin "8") (pinfunction "GND_8") (pintype "power_in"))
      (node (ref "D17") (pin "3") (pinfunction "GND_3") (pintype "power_in"))
      (node (ref "D17") (pin "8") (pinfunction "GND_8") (pintype "power_in"))
      (node (ref "D18") (pin "3") (pinfunction "GND_3") (pintype "power_in"))
      (node (ref "D18") (pin "8") (pinfunction "GND_8") (pintype "power_in"))
      (node (ref "D19") (pin "3") (pinfunction "GND_3") (pintype "power_in"))
      (node (ref "D19") (pin "8") (pinfunction "GND_8") (pintype "power_in"))
      (node (ref "D2") (pin "3") (pinfunction "GND_3") (pintype "power_in"))
      (node (ref "D2") (pin "8") (pinfunction "GND_8") (pintype "power_in"))
      (node (ref "D20") (pin "3") (pinfunction "GND_3") (pintype "power_in"))
      (node (ref "D20") (pin "8") (pinfunction "GND_8") (pintype "power_in"))
      (node (ref "D21") (pin "3") (pinfunction "GND_3") (pintype "power_in"))
      (node (ref "D21") (pin "8") (pinfunction "GND_8") (pintype "power_in"))
      (node (ref "D3") (pin "3") (pinfunction "GND_3") (pintype "power_in"))
      (node (ref "D3") (pin "8") (pinfunction "GND_8") (pintype "power_in"))
      (node (ref "D4") (pin "3") (pinfunction "GND_3") (pintype "power_in"))
      (node (ref "D4") (pin "8") (pinfunction "GND_8") (pintype "power_in"))
      (node (ref "D5") (pin "3") (pinfunction "GND_3") (pintype "power_in"))
      (node (ref "D5") (pin "8") (pinfunction "GND_8") (pintype "power_in"))
      (node (ref "D6") (pin "3") (pinfunction "GND_3") (pintype "power_in"))
      (node (ref "D6") (pin "8") (pinfunction "GND_8") (pintype "power_in"))
      (node (ref "D7") (pin "3") (pinfunction "GND_3") (pintype "power_in"))
      (node (ref "D7") (pin "8") (pinfunction "GND_8") (pintype "power_in"))
      (node (ref "D8") (pin "3") (pinfunction "GND_3") (pintype "power_in"))
      (node (ref "D8") (pin "8") (pinfunction "GND_8") (pintype "power_in"))
      (node (ref "D9") (pin "3") (pinfunction "GND_3") (pintype "power_in"))
      (node (ref "D9") (pin "8") (pinfunction "GND_8") (pintype "power_in"))
      (node (ref "J1") (pin "1") (pinfunction "1_1") (pintype "passive"))
      (node (ref "J1") (pin "102") (pinfunction "102_102") (pintype "passive"))
      (node (ref "J1") (pin "107") (pinfunction "107_107") (pintype "passive"))
      (node (ref "J1") (pin "113") (pinfunction "113_113") (pintype "passive"))
      (node (ref "J1") (pin "119") (pinfunction "119_119") (pintype "passive"))
      (node (ref "J1") (pin "125") (pinfunction "125_125") (pintype "passive"))
      (node (ref "J1") (pin "129") (pinfunction "129_129") (pintype "passive"))
      (node (ref "J1") (pin "13") (pinfunction "13_13") (pintype "passive"))
      (node (ref "J1") (pin "132") (pinfunction "132_132") (pintype "passive"))
      (node (ref "J1") (pin "135") (pinfunction "135_135") (pintype "passive"))
      (node (ref "J1") (pin "138") (pinfunction "138_138") (pintype "passive"))
      (node (ref "J1") (pin "14") (pinfunction "14_14") (pintype "passive"))
      (node (ref "J1") (pin "141") (pinfunction "141_141") (pintype "passive"))
      (node (ref "J1") (pin "144") (pinfunction "144_144") (pintype "passive"))
      (node (ref "J1") (pin "146") (pinfunction "146_146") (pintype "passive"))
      (node (ref "J1") (pin "147") (pinfunction "147_147") (pintype "passive"))
      (node (ref "J1") (pin "152") (pinfunction "152_152") (pintype "passive"))
      (node (ref "J1") (pin "153") (pinfunction "153_153") (pintype "passive"))
      (node (ref "J1") (pin "158") (pinfunction "158_158") (pintype "passive"))
      (node (ref "J1") (pin "159") (pinfunction "159_159") (pintype "passive"))
      (node (ref "J1") (pin "164") (pinfunction "164_164") (pintype "passive"))
      (node (ref "J1") (pin "165") (pinfunction "165_165") (pintype "passive"))
      (node (ref "J1") (pin "170") (pinfunction "170_170") (pintype "passive"))
      (node (ref "J1") (pin "171") (pinfunction "171_171") (pintype "passive"))
      (node (ref "J1") (pin "176") (pinfunction "176_176") (pintype "passive"))
      (node (ref "J1") (pin "177") (pinfunction "177_177") (pintype "passive"))
      (node (ref "J1") (pin "19") (pinfunction "19_19") (pintype "passive"))
      (node (ref "J1") (pin "2") (pinfunction "2_2") (pintype "passive"))
      (node (ref "J1") (pin "20") (pinfunction "20_20") (pintype "passive"))
      (node (ref "J1") (pin "200") (pinfunction "200_200") (pintype "passive"))
      (node (ref "J1") (pin "201") (pinfunction "201_201") (pintype "passive"))
      (node (ref "J1") (pin "231") (pinfunction "231_231") (pintype "passive"))
      (node (ref "J1") (pin "241") (pinfunction "241_241") (pintype "passive"))
      (node (ref "J1") (pin "242") (pinfunction "242_242") (pintype "passive"))
      (node (ref "J1") (pin "243") (pinfunction "243_243") (pintype "passive"))
      (node (ref "J1") (pin "244") (pinfunction "244_244") (pintype "passive"))
      (node (ref "J1") (pin "245") (pinfunction "245_245") (pintype "passive"))
      (node (ref "J1") (pin "246") (pinfunction "246_246") (pintype "passive"))
      (node (ref "J1") (pin "247") (pinfunction "247_247") (pintype "passive"))
      (node (ref "J1") (pin "248") (pinfunction "248_248") (pintype "passive"))
      (node (ref "J1") (pin "249") (pinfunction "249_249") (pintype "passive"))
      (node (ref "J1") (pin "25") (pinfunction "25_25") (pintype "passive"))
      (node (ref "J1") (pin "250") (pinfunction "250_250") (pintype "passive"))
      (node (ref "J1") (pin "26") (pinfunction "26_26") (pintype "passive"))
      (node (ref "J1") (pin "261") (pinfunction "MNT_1_261") (pintype "passive"))
      (node (ref "J1") (pin "262") (pinfunction "MNT_2_262") (pintype "passive"))
      (node (ref "J1") (pin "31") (pinfunction "31_31") (pintype "passive"))
      (node (ref "J1") (pin "32") (pinfunction "32_32") (pintype "passive"))
      (node (ref "J1") (pin "37") (pinfunction "37_37") (pintype "passive"))
      (node (ref "J1") (pin "38") (pinfunction "38_38") (pintype "passive"))
      (node (ref "J1") (pin "43") (pinfunction "43_43") (pintype "passive"))
      (node (ref "J1") (pin "44") (pinfunction "44_44") (pintype "passive"))
      (node (ref "J1") (pin "49") (pinfunction "49_49") (pintype "passive"))
      (node (ref "J1") (pin "50") (pinfunction "50_50") (pintype "passive"))
      (node (ref "J1") (pin "55") (pinfunction "55_55") (pintype "passive"))
      (node (ref "J1") (pin "56") (pinfunction "56_56") (pintype "passive"))
      (node (ref "J1") (pin "61") (pinfunction "61_61") (pintype "passive"))
      (node (ref "J1") (pin "62") (pinfunction "62_62") (pintype "passive"))
      (node (ref "J1") (pin "67") (pinfunction "67_67") (pintype "passive"))
      (node (ref "J1") (pin "68") (pinfunction "68_68") (pintype "passive"))
      (node (ref "J1") (pin "7") (pinfunction "7_7") (pintype "passive"))
      (node (ref "J1") (pin "73") (pinfunction "73_73") (pintype "passive"))
      (node (ref "J1") (pin "74") (pinfunction "74_74") (pintype "passive"))
      (node (ref "J1") (pin "79") (pinfunction "79_79") (pintype "passive"))
      (node (ref "J1") (pin "8") (pinfunction "8_8") (pintype "passive"))
      (node (ref "J1") (pin "80") (pinfunction "80_80") (pintype "passive"))
      (node (ref "J1") (pin "85") (pinfunction "85_85") (pintype "passive"))
      (node (ref "J1") (pin "86") (pinfunction "86_86") (pintype "passive"))
      (node (ref "J17") (pin "2") (pinfunction "2_2") (pintype "passive"))
      (node (ref "MP1") (pin "1") (pinfunction "1_1") (pintype "passive"))
      (node (ref "MP2") (pin "1") (pinfunction "1_1") (pintype "passive"))
      (node (ref "Q9") (pin "1") (pinfunction "Source1_1") (pintype "passive"))
      (node (ref "Q9") (pin "4") (pinfunction "Source2_4") (pintype "passive"))
      (node (ref "R127") (pin "2") (pinfunction "2_2") (pintype "passive"))
      (node (ref "R172") (pin "1") (pinfunction "1_1") (pintype "passive"))
      (node (ref "R173") (pin "1") (pinfunction "1_1") (pintype "passive"))
      (node (ref "R316") (pin "1") (pinfunction "1_1") (pintype "passive"))
      (node (ref "U11") (pin "3") (pinfunction "GND_3") (pintype "power_in"))
      (node (ref "U12") (pin "3") (pinfunction "GND_3") (pintype "power_in"))
      (node (ref "U24") (pin "1") (pinfunction "GND_1") (pintype "power_in"))
    )
    (net (code "136") (name "JETSON_1V8_REF") (class "Default")
      (node (ref "C103") (pin "1") (pinfunction "1_1") (pintype "passive"))
      (node (ref "C116") (pin "1") (pinfunction "1_1") (pintype "passive"))
      (node (ref "C213") (pin "1") (pinfunction "1_1") (pintype "passive"))
      (node (ref "Q18") (pin "1") (pinfunction "G_1") (pintype "passive"))
      (node (ref "Q19") (pin "1") (pinfunction "G_1") (pintype "passive"))
      (node (ref "Q20") (pin "1") (pinfunction "G_1") (pintype "passive"))
      (node (ref "Q21") (pin "1") (pinfunction "G_1") (pintype "passive"))
      (node (ref "Q22") (pin "1") (pinfunction "G_1") (pintype "passive"))
      (node (ref "Q7") (pin "1") (pinfunction "G_1") (pintype "passive"))
      (node (ref "Q8") (pin "1") (pinfunction "G_1") (pintype "passive"))
      (node (ref "R175") (pin "2") (pinfunction "2_2") (pintype "passive"))
      (node (ref "R176") (pin "2") (pinfunction "2_2") (pintype "passive"))
      (node (ref "R234") (pin "2") (pinfunction "2_2") (pintype "passive"))
      (node (ref "R265") (pin "2") (pinfunction "2_2") (pintype "passive"))
      (node (ref "R268") (pin "2") (pinfunction "2_2") (pintype "passive"))
      (node (ref "R271") (pin "2") (pinfunction "2_2") (pintype "passive"))
      (node (ref "R274") (pin "2") (pinfunction "2_2") (pintype "passive"))
      (node (ref "R355") (pin "2") (pinfunction "2_2") (pintype "passive"))
      (node (ref "R62") (pin "2") (pinfunction "2_2") (pintype "passive"))
      (node (ref "R92") (pin "2") (pinfunction "2_2") (pintype "passive"))
      (node (ref "U11") (pin "5") (pinfunction "VCC_5") (pintype "power_in"))
      (node (ref "U12") (pin "5") (pinfunction "VCC_5") (pintype "power_in"))
      (node (ref "U24") (pin "2") (pinfunction "VOUT_2") (pintype "power_in"))
      (node (ref "U24") (pin "4") (pinfunction "VOUT_4") (pintype "power_in"))
    )
    (net (code "137") (name "Net-(Q7-D)") (class "Default")
      (node (ref "Q7") (pin "3") (pinfunction "D_3") (pintype "passive"))
      (node (ref "R63") (pin "1") (pinfunction "1_1") (pintype "passive"))
      (node (ref "R64") (pin "1") (pinfunction "1_1") (pintype "passive"))
    )
    (net (code "138") (name "Net-(Q8-D)") (class "Default")
      (node (ref "Q8") (pin "3") (pinfunction "D_3") (pintype "passive"))
      (node (ref "R118") (pin "1") (pinfunction "1_1") (pintype "passive"))
      (node (ref "R122") (pin "1") (pinfunction "1_1") (pintype "passive"))
    )
    (net (code "139") (name "Net-(Q9A-Gate1)") (class "Default")
      (node (ref "Q9") (pin "2") (pinfunction "Gate1_2") (pintype "passive"))
      (node (ref "R128") (pin "2") (pinfunction "2_2") (pintype "passive"))
      (node (ref "R172") (pin "2") (pinfunction "2_2") (pintype "passive"))
    )
    (net (code "140") (name "Net-(Q9B-Gate2)") (class "Default")
      (node (ref "Q9") (pin "5") (pinfunction "Gate2_5") (pintype "passive"))
      (node (ref "R129") (pin "2") (pinfunction "2_2") (pintype "passive"))
      (node (ref "R173") (pin "2") (pinfunction "2_2") (pintype "passive"))
    )
    (net (code "141") (name "Net-(Q18-D)") (class "Default")
      (node (ref "Q18") (pin "3") (pinfunction "D_3") (pintype "passive"))
      (node (ref "R235") (pin "1") (pinfunction "1_1") (pintype "passive"))
      (node (ref "R264") (pin "1") (pinfunction "1_1") (pintype "passive"))
    )
    (net (code "142") (name "Net-(Q19-D)") (class "Default")
      (node (ref "Q19") (pin "3") (pinfunction "D_3") (pintype "passive"))
      (node (ref "R266") (pin "1") (pinfunction "1_1") (pintype "passive"))
      (node (ref "R267") (pin "1") (pinfunction "1_1") (pintype "passive"))
    )
    (net (code "143") (name "Net-(Q20-D)") (class "Default")
      (node (ref "Q20") (pin "3") (pinfunction "D_3") (pintype "passive"))
      (node (ref "R269") (pin "1") (pinfunction "1_1") (pintype "passive"))
      (node (ref "R270") (pin "1") (pinfunction "1_1") (pintype "passive"))
    )
    (net (code "144") (name "Net-(Q21-D)") (class "Default")
      (node (ref "Q21") (pin "3") (pinfunction "D_3") (pintype "passive"))
      (node (ref "R272") (pin "1") (pinfunction "1_1") (pintype "passive"))
      (node (ref "R273") (pin "1") (pinfunction "1_1") (pintype "passive"))
    )
    (net (code "145") (name "Net-(Q22-D)") (class "Default")
      (node (ref "Q22") (pin "3") (pinfunction "D_3") (pintype "passive"))
      (node (ref "R275") (pin "1") (pinfunction "1_1") (pintype "passive"))
      (node (ref "R276") (pin "1") (pinfunction "1_1") (pintype "passive"))
    )
    (net (code "146") (name "unconnected-(D18-IO1-Pad1)") (class "Default")
      (node (ref "D18") (pin "1") (pinfunction "IO1_1") (pintype "bidirectional"))
    )
    (net (code "147") (name "unconnected-(D18-IO2-Pad2)") (class "Default")
      (node (ref "D18") (pin "2") (pinfunction "IO2_2") (pintype "bidirectional"))
    )
    (net (code "148") (name "unconnected-(D18-NC-Pad9)") (class "Default")
      (node (ref "D18") (pin "9") (pinfunction "NC_9") (pintype "passive"))
    )
    (net (code "149") (name "unconnected-(D18-NC-Pad10)") (class "Default")
      (node (ref "D18") (pin "10") (pinfunction "NC_10") (pintype "passive"))
    )
    (net (code "150") (name "unconnected-(J1-Pad9)") (class "Default")
      (node (ref "J1") (pin "9") (pinfunction "9_9") (pintype "passive+no_connect"))
    )
    (net (code "151") (name "unconnected-(J1-Pad11)") (class "Default")
      (node (ref "J1") (pin "11") (pinfunction "11_11") (pintype "passive+no_connect"))
    )
    (net (code "152") (name "unconnected-(J1-Pad27)") (class "Default")
      (node (ref "J1") (pin "27") (pinfunction "27_27") (pintype "passive+no_connect"))
    )
    (net (code "153") (name "unconnected-(J1-Pad29)") (class "Default")
      (node (ref "J1") (pin "29") (pinfunction "29_29") (pintype "passive+no_connect"))
    )
    (net (code "154") (name "unconnected-(J1-Pad39)") (class "Default")
      (node (ref "J1") (pin "39") (pinfunction "39_39") (pintype "passive+no_connect"))
    )
    (net (code "155") (name "unconnected-(J1-Pad40)") (class "Default")
      (node (ref "J1") (pin "40") (pinfunction "40_40") (pintype "passive+no_connect"))
    )
    (net (code "156") (name "unconnected-(J1-Pad41)") (class "Default")
      (node (ref "J1") (pin "41") (pinfunction "41_41") (pintype "passive+no_connect"))
    )
    (net (code "157") (name "unconnected-(J1-Pad42)") (class "Default")
      (node (ref "J1") (pin "42") (pinfunction "42_42") (pintype "passive+no_connect"))
    )
    (net (code "158") (name "unconnected-(J1-Pad45)") (class "Default")
      (node (ref "J1") (pin "45") (pinfunction "45_45") (pintype "passive+no_connect"))
    )
    (net (code "159") (name "unconnected-(J1-Pad46)") (class "Default")
      (node (ref "J1") (pin "46") (pinfunction "46_46") (pintype "passive+no_connect"))
    )
    (net (code "160") (name "unconnected-(J1-Pad47)") (class "Default")
      (node (ref "J1") (pin "47") (pinfunction "47_47") (pintype "passive+no_connect"))
    )
    (net (code "161") (name "unconnected-(J1-Pad48)") (class "Default")
      (node (ref "J1") (pin "48") (pinfunction "48_48") (pintype "passive+no_connect"))
    )
    (net (code "162") (name "unconnected-(J1-Pad51)") (class "Default")
      (node (ref "J1") (pin "51") (pinfunction "51_51") (pintype "passive+no_connect"))
    )
    (net (code "163") (name "unconnected-(J1-Pad52)") (class "Default")
      (node (ref "J1") (pin "52") (pinfunction "52_52") (pintype "passive+no_connect"))
    )
    (net (code "164") (name "unconnected-(J1-Pad53)") (class "Default")
      (node (ref "J1") (pin "53") (pinfunction "53_53") (pintype "passive+no_connect"))
    )
    (net (code "165") (name "unconnected-(J1-Pad54)") (class "Default")
      (node (ref "J1") (pin "54") (pinfunction "54_54") (pintype "passive+no_connect"))
    )
    (net (code "166") (name "unconnected-(J1-Pad57)") (class "Default")
      (node (ref "J1") (pin "57") (pinfunction "57_57") (pintype "passive+no_connect"))
    )
    (net (code "167") (name "unconnected-(J1-Pad58)") (class "Default")
      (node (ref "J1") (pin "58") (pinfunction "58_58") (pintype "passive+no_connect"))
    )
    (net (code "168") (name "unconnected-(J1-Pad59)") (class "Default")
      (node (ref "J1") (pin "59") (pinfunction "59_59") (pintype "passive+no_connect"))
    )
    (net (code "169") (name "unconnected-(J1-Pad60)") (class "Default")
      (node (ref "J1") (pin "60") (pinfunction "60_60") (pintype "passive+no_connect"))
    )
    (net (code "170") (name "unconnected-(J1-Pad64)") (class "Default")
      (node (ref "J1") (pin "64") (pinfunction "64_64") (pintype "passive+no_connect"))
    )
    (net (code "171") (name "unconnected-(J1-Pad66)") (class "Default")
      (node (ref "J1") (pin "66") (pinfunction "66_66") (pintype "passive+no_connect"))
    )
    (net (code "172") (name "unconnected-(J1-Pad70)") (class "Default")
      (node (ref "J1") (pin "70") (pinfunction "70_70") (pintype "passive+no_connect"))
    )
    (net (code "173") (name "unconnected-(J1-Pad72)") (class "Default")
      (node (ref "J1") (pin "72") (pinfunction "72_72") (pintype "passive+no_connect"))
    )
    (net (code "174") (name "unconnected-(J1-Pad76)") (class "Default")
      (node (ref "J1") (pin "76") (pinfunction "76_76") (pintype "passive+no_connect"))
    )
    (net (code "175") (name "unconnected-(J1-Pad78)") (class "Default")
      (node (ref "J1") (pin "78") (pinfunction "78_78") (pintype "passive+no_connect"))
    )
    (net (code "176") (name "unconnected-(J1-Pad82)") (class "Default")
      (node (ref "J1") (pin "82") (pinfunction "82_82") (pintype "passive+no_connect"))
    )
    (net (code "177") (name "unconnected-(J1-Pad84)") (class "Default")
      (node (ref "J1") (pin "84") (pinfunction "84_84") (pintype "passive+no_connect"))
    )
    (net (code "178") (name "unconnected-(J1-Pad88)") (class "Default")
      (node (ref "J1") (pin "88") (pinfunction "88_88") (pintype "passive+no_connect"))
    )
    (net (code "179") (name "unconnected-(J1-Pad89)") (class "Default")
      (node (ref "J1") (pin "89") (pinfunction "89_89") (pintype "passive+no_connect"))
    )
    (net (code "180") (name "unconnected-(J1-Pad90)") (class "Default")
      (node (ref "J1") (pin "90") (pinfunction "90_90") (pintype "passive+no_connect"))
    )
    (net (code "181") (name "unconnected-(J1-Pad91)") (class "Default")
      (node (ref "J1") (pin "91") (pinfunction "91_91") (pintype "passive+no_connect"))
    )
    (net (code "182") (name "unconnected-(J1-Pad92)") (class "Default")
      (node (ref "J1") (pin "92") (pinfunction "92_92") (pintype "passive+no_connect"))
    )
    (net (code "183") (name "unconnected-(J1-Pad93)") (class "Default")
      (node (ref "J1") (pin "93") (pinfunction "93_93") (pintype "passive+no_connect"))
    )
    (net (code "184") (name "unconnected-(J1-Pad95)") (class "Default")
      (node (ref "J1") (pin "95") (pinfunction "95_95") (pintype "passive+no_connect"))
    )
    (net (code "185") (name "unconnected-(J1-Pad97)") (class "Default")
      (node (ref "J1") (pin "97") (pinfunction "97_97") (pintype "passive+no_connect"))
    )
    (net (code "186") (name "unconnected-(J1-Pad99)") (class "Default")
      (node (ref "J1") (pin "99") (pinfunction "99_99") (pintype "passive+no_connect"))
    )
    (net (code "187") (name "unconnected-(J1-Pad101)") (class "Default")
      (node (ref "J1") (pin "101") (pinfunction "101_101") (pintype "passive+no_connect"))
    )
    (net (code "188") (name "unconnected-(J1-Pad103)") (class "Default")
      (node (ref "J1") (pin "103") (pinfunction "103_103") (pintype "passive+no_connect"))
    )
    (net (code "189") (name "unconnected-(J1-Pad105)") (class "Default")
      (node (ref "J1") (pin "105") (pinfunction "105_105") (pintype "passive+no_connect"))
    )
    (net (code "190") (name "unconnected-(J1-Pad116)") (class "Default")
      (node (ref "J1") (pin "116") (pinfunction "116_116") (pintype "passive+no_connect"))
    )
    (net (code "191") (name "unconnected-(J1-Pad121)") (class "Default")
      (node (ref "J1") (pin "121") (pinfunction "121_121") (pintype "passive+no_connect"))
    )
    (net (code "192") (name "unconnected-(J1-Pad122)") (class "Default")
      (node (ref "J1") (pin "122") (pinfunction "122_122") (pintype "passive+no_connect"))
    )
    (net (code "193") (name "unconnected-(J1-Pad123)") (class "Default")
      (node (ref "J1") (pin "123") (pinfunction "123_123") (pintype "passive+no_connect"))
    )
    (net (code "194") (name "unconnected-(J1-Pad167)") (class "Default")
      (node (ref "J1") (pin "167") (pinfunction "167_167") (pintype "passive+no_connect"))
    )
    (net (code "195") (name "unconnected-(J1-Pad169)") (class "Default")
      (node (ref "J1") (pin "169") (pinfunction "169_169") (pintype "passive+no_connect"))
    )
    (net (code "196") (name "unconnected-(J1-Pad172)") (class "Default")
      (node (ref "J1") (pin "172") (pinfunction "172_172") (pintype "passive+no_connect"))
    )
    (net (code "197") (name "unconnected-(J1-Pad173)") (class "Default")
      (node (ref "J1") (pin "173") (pinfunction "173_173") (pintype "passive+no_connect"))
    )
    (net (code "198") (name "unconnected-(J1-Pad174)") (class "Default")
      (node (ref "J1") (pin "174") (pinfunction "174_174") (pintype "passive+no_connect"))
    )
    (net (code "199") (name "unconnected-(J1-Pad175)") (class "Default")
      (node (ref "J1") (pin "175") (pinfunction "175_175") (pintype "passive+no_connect"))
    )
    (net (code "200") (name "unconnected-(J1-Pad182)") (class "Default")
      (node (ref "J1") (pin "182") (pinfunction "182_182") (pintype "passive+no_connect"))
    )
    (net (code "201") (name "unconnected-(J1-Pad183)") (class "Default")
      (node (ref "J1") (pin "183") (pinfunction "183_183") (pintype "passive+no_connect"))
    )
    (net (code "202") (name "unconnected-(J1-Pad203)") (class "Default")
      (node (ref "J1") (pin "203") (pinfunction "203_203") (pintype "passive+no_connect"))
    )
    (net (code "203") (name "unconnected-(J1-Pad205)") (class "Default")
      (node (ref "J1") (pin "205") (pinfunction "205_205") (pintype "passive+no_connect"))
    )
    (net (code "204") (name "unconnected-(J1-Pad207)") (class "Default")
      (node (ref "J1") (pin "207") (pinfunction "207_207") (pintype "passive+no_connect"))
    )
    (net (code "205") (name "unconnected-(J1-Pad209)") (class "Default")
      (node (ref "J1") (pin "209") (pinfunction "209_209") (pintype "passive+no_connect"))
    )
    (net (code "206") (name "unconnected-(J1-Pad219)") (class "Default")
      (node (ref "J1") (pin "219") (pinfunction "219_219") (pintype "passive+no_connect"))
    )
    (net (code "207") (name "unconnected-(J1-Pad220)") (class "Default")
      (node (ref "J1") (pin "220") (pinfunction "220_220") (pintype "passive+no_connect"))
    )
    (net (code "208") (name "unconnected-(J1-Pad221)") (class "Default")
      (node (ref "J1") (pin "221") (pinfunction "221_221") (pintype "passive+no_connect"))
    )
    (net (code "209") (name "unconnected-(J1-Pad222)") (class "Default")
      (node (ref "J1") (pin "222") (pinfunction "222_222") (pintype "passive+no_connect"))
    )
    (net (code "210") (name "unconnected-(J1-Pad223)") (class "Default")
      (node (ref "J1") (pin "223") (pinfunction "223_223") (pintype "passive+no_connect"))
    )
    (net (code "211") (name "unconnected-(J1-Pad224)") (class "Default")
      (node (ref "J1") (pin "224") (pinfunction "224_224") (pintype "passive+no_connect"))
    )
    (net (code "212") (name "unconnected-(J1-Pad225)") (class "Default")
      (node (ref "J1") (pin "225") (pinfunction "225_225") (pintype "passive+no_connect"))
    )
    (net (code "213") (name "unconnected-(J1-Pad226)") (class "Default")
      (node (ref "J1") (pin "226") (pinfunction "226_226") (pintype "passive+no_connect"))
    )
    (net (code "214") (name "unconnected-(J1-Pad227)") (class "Default")
      (node (ref "J1") (pin "227") (pinfunction "227_227") (pintype "passive+no_connect"))
    )
    (net (code "215") (name "unconnected-(J1-Pad229)") (class "Default")
      (node (ref "J1") (pin "229") (pinfunction "229_229") (pintype "passive+no_connect"))
    )
    (net (code "216") (name "unconnected-(J1-Pad232)") (class "Default")
      (node (ref "J1") (pin "232") (pinfunction "232_232") (pintype "passive+no_connect"))
    )
    (net (code "217") (name "unconnected-(J1-Pad234)") (class "Default")
      (node (ref "J1") (pin "234") (pinfunction "234_234") (pintype "passive+no_connect"))
    )
    (net (code "218") (name "unconnected-(U11-NC-Pad1)") (class "Default")
      (node (ref "U11") (pin "1") (pinfunction "NC_1") (pintype "passive+no_connect"))
    )
    (net (code "219") (name "unconnected-(U12-NC-Pad1)") (class "Default")
      (node (ref "U12") (pin "1") (pinfunction "NC_1") (pintype "passive+no_connect"))
    )
  )
)
